# Board.net
KiCad netlist of a schematic drawn in EAGLE
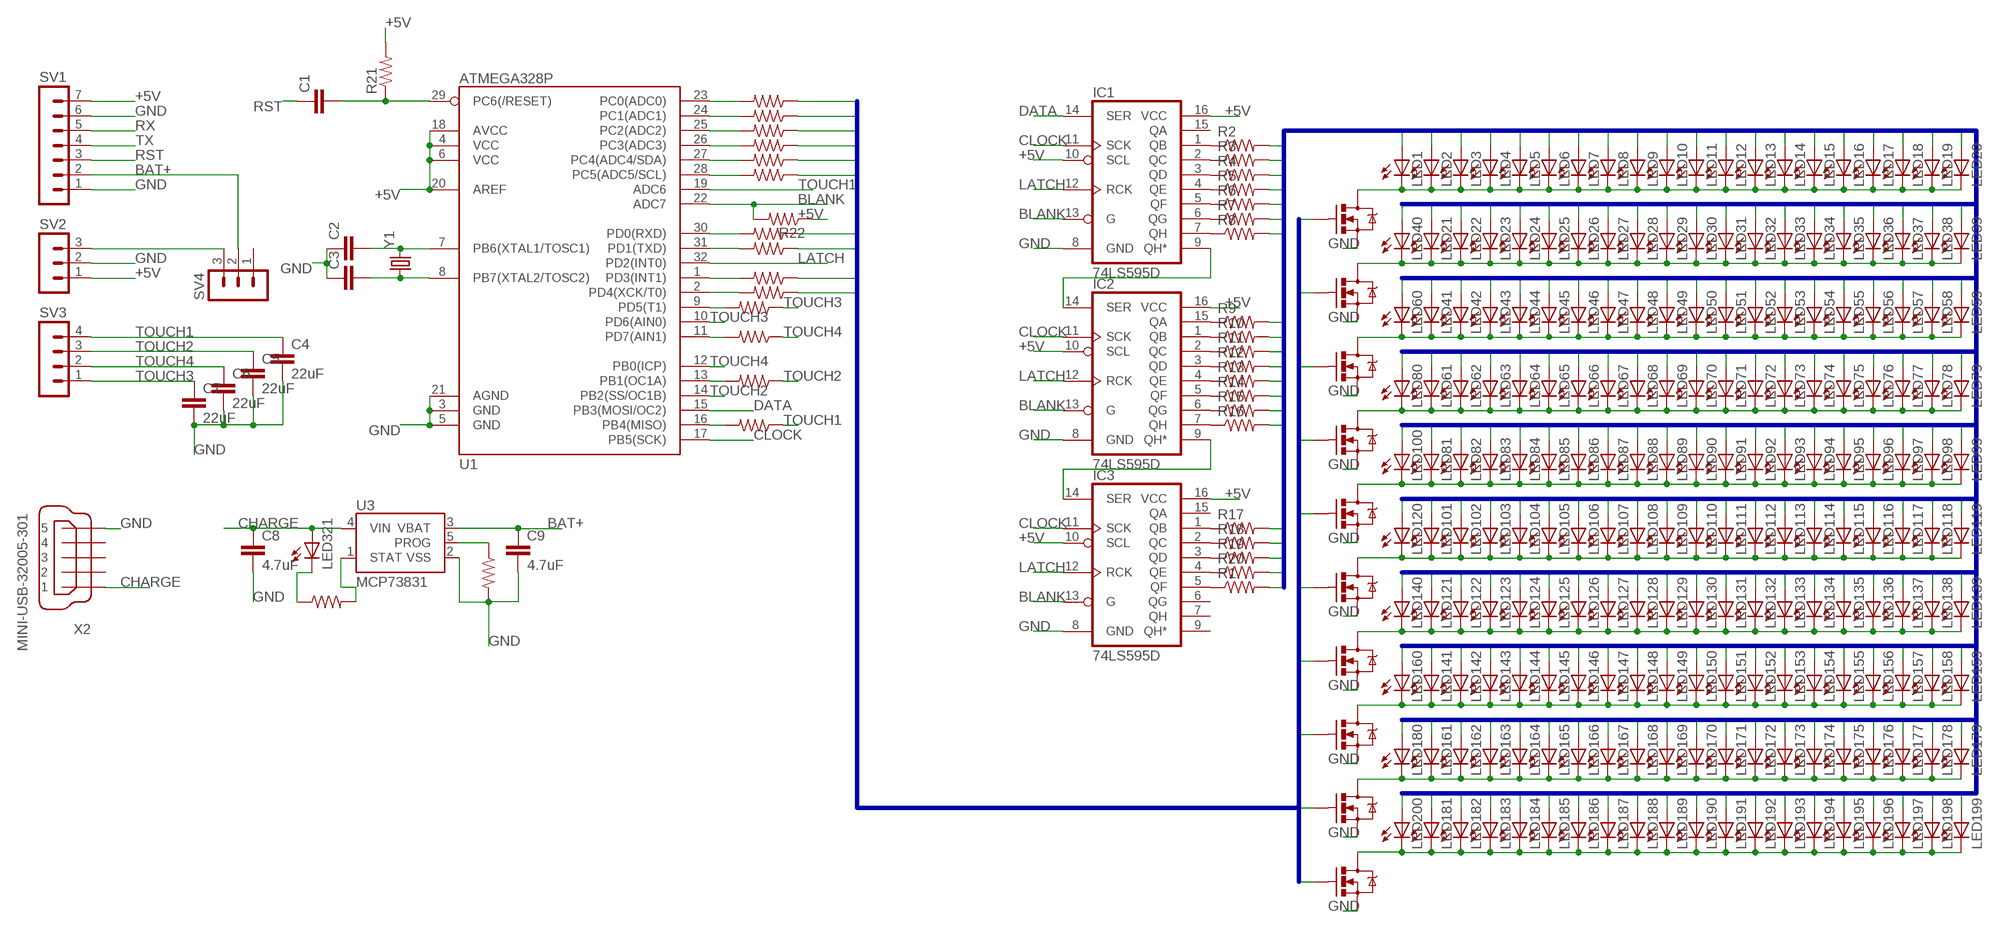
[diagram p0: schematic, sheet 1]

(export (version "E")
  (design (tool "Eeschema 10.0.6"))
  (components
    (comp (ref "2K")
      (value "2K")
      (footprint "eagle-import:0603-RES")
      (libsource (lib "eagle-import") (part "100OHM1/10W1%(0603)"))
    )
    (comp (ref "470R")
      (value "470R")
      (footprint "eagle-import:0603-RES")
      (libsource (lib "eagle-import") (part "100OHM1/10W1%(0603)"))
    )
    (comp (ref "C1")
      (value "CAPPTH1")
      (footprint "eagle-import:CAP-PTH-5MM")
      (libsource (lib "eagle-import") (part "CAPPTH1"))
    )
    (comp (ref "C2")
      (value "22uF")
      (footprint "eagle-import:0805")
      (libsource (lib "eagle-import") (part "22UF-6.3V-20%(0805)"))
    )
    (comp (ref "C3")
      (value "22uF")
      (footprint "eagle-import:0805")
      (libsource (lib "eagle-import") (part "22UF-6.3V-20%(0805)"))
    )
    (comp (ref "C4")
      (value "22uF")
      (footprint "eagle-import:0805")
      (libsource (lib "eagle-import") (part "22UF-6.3V-20%(0805)"))
    )
    (comp (ref "C5")
      (value "22uF")
      (footprint "eagle-import:0805")
      (libsource (lib "eagle-import") (part "22UF-6.3V-20%(0805)"))
    )
    (comp (ref "C6")
      (value "22uF")
      (footprint "eagle-import:0805")
      (libsource (lib "eagle-import") (part "22UF-6.3V-20%(0805)"))
    )
    (comp (ref "C7")
      (value "22uF")
      (footprint "eagle-import:0805")
      (libsource (lib "eagle-import") (part "22UF-6.3V-20%(0805)"))
    )
    (comp (ref "C8")
      (value "4.7uF")
      (footprint "eagle-import:0603-CAP")
      (libsource (lib "eagle-import") (part "0.1UF-25V(+80/-20%)(0603)"))
    )
    (comp (ref "C9")
      (value "4.7uF")
      (footprint "eagle-import:0603-CAP")
      (libsource (lib "eagle-import") (part "0.1UF-25V(+80/-20%)(0603)"))
    )
    (comp (ref "IC1")
      (value "74LS595D")
      (footprint "eagle-import:SO16")
      (libsource (lib "eagle-import") (part "74595DLS"))
    )
    (comp (ref "IC2")
      (value "74LS595D")
      (footprint "eagle-import:SO16")
      (libsource (lib "eagle-import") (part "74595DLS"))
    )
    (comp (ref "IC3")
      (value "74LS595D")
      (footprint "eagle-import:SO16")
      (libsource (lib "eagle-import") (part "74595DLS"))
    )
    (comp (ref "LED1")
      (value "LED0603")
      (footprint "eagle-import:LED-0603")
      (libsource (lib "eagle-import") (part "LED0603"))
    )
    (comp (ref "LED2")
      (value "LED0603")
      (footprint "eagle-import:LED-0603")
      (libsource (lib "eagle-import") (part "LED0603"))
    )
    (comp (ref "LED3")
      (value "LED0603")
      (footprint "eagle-import:LED-0603")
      (libsource (lib "eagle-import") (part "LED0603"))
    )
    (comp (ref "LED4")
      (value "LED0603")
      (footprint "eagle-import:LED-0603")
      (libsource (lib "eagle-import") (part "LED0603"))
    )
    (comp (ref "LED5")
      (value "LED0603")
      (footprint "eagle-import:LED-0603")
      (libsource (lib "eagle-import") (part "LED0603"))
    )
    (comp (ref "LED6")
      (value "LED0603")
      (footprint "eagle-import:LED-0603")
      (libsource (lib "eagle-import") (part "LED0603"))
    )
    (comp (ref "LED7")
      (value "LED0603")
      (footprint "eagle-import:LED-0603")
      (libsource (lib "eagle-import") (part "LED0603"))
    )
    (comp (ref "LED8")
      (value "LED0603")
      (footprint "eagle-import:LED-0603")
      (libsource (lib "eagle-import") (part "LED0603"))
    )
    (comp (ref "LED9")
      (value "LED0603")
      (footprint "eagle-import:LED-0603")
      (libsource (lib "eagle-import") (part "LED0603"))
    )
    (comp (ref "LED10")
      (value "LED0603")
      (footprint "eagle-import:LED-0603")
      (libsource (lib "eagle-import") (part "LED0603"))
    )
    (comp (ref "LED11")
      (value "LED0603")
      (footprint "eagle-import:LED-0603")
      (libsource (lib "eagle-import") (part "LED0603"))
    )
    (comp (ref "LED12")
      (value "LED0603")
      (footprint "eagle-import:LED-0603")
      (libsource (lib "eagle-import") (part "LED0603"))
    )
    (comp (ref "LED13")
      (value "LED0603")
      (footprint "eagle-import:LED-0603")
      (libsource (lib "eagle-import") (part "LED0603"))
    )
    (comp (ref "LED14")
      (value "LED0603")
      (footprint "eagle-import:LED-0603")
      (libsource (lib "eagle-import") (part "LED0603"))
    )
    (comp (ref "LED15")
      (value "LED0603")
      (footprint "eagle-import:LED-0603")
      (libsource (lib "eagle-import") (part "LED0603"))
    )
    (comp (ref "LED16")
      (value "LED0603")
      (footprint "eagle-import:LED-0603")
      (libsource (lib "eagle-import") (part "LED0603"))
    )
    (comp (ref "LED17")
      (value "LED0603")
      (footprint "eagle-import:LED-0603")
      (libsource (lib "eagle-import") (part "LED0603"))
    )
    (comp (ref "LED18")
      (value "LED0603")
      (footprint "eagle-import:LED-0603")
      (libsource (lib "eagle-import") (part "LED0603"))
    )
    (comp (ref "LED19")
      (value "LED0603")
      (footprint "eagle-import:LED-0603")
      (libsource (lib "eagle-import") (part "LED0603"))
    )
    (comp (ref "LED20")
      (value "LED0603")
      (footprint "eagle-import:LED-0603")
      (libsource (lib "eagle-import") (part "LED0603"))
    )
    (comp (ref "LED21")
      (value "LED0603")
      (footprint "eagle-import:LED-0603")
      (libsource (lib "eagle-import") (part "LED0603"))
    )
    (comp (ref "LED22")
      (value "LED0603")
      (footprint "eagle-import:LED-0603")
      (libsource (lib "eagle-import") (part "LED0603"))
    )
    (comp (ref "LED23")
      (value "LED0603")
      (footprint "eagle-import:LED-0603")
      (libsource (lib "eagle-import") (part "LED0603"))
    )
    (comp (ref "LED24")
      (value "LED0603")
      (footprint "eagle-import:LED-0603")
      (libsource (lib "eagle-import") (part "LED0603"))
    )
    (comp (ref "LED25")
      (value "LED0603")
      (footprint "eagle-import:LED-0603")
      (libsource (lib "eagle-import") (part "LED0603"))
    )
    (comp (ref "LED26")
      (value "LED0603")
      (footprint "eagle-import:LED-0603")
      (libsource (lib "eagle-import") (part "LED0603"))
    )
    (comp (ref "LED27")
      (value "LED0603")
      (footprint "eagle-import:LED-0603")
      (libsource (lib "eagle-import") (part "LED0603"))
    )
    (comp (ref "LED28")
      (value "LED0603")
      (footprint "eagle-import:LED-0603")
      (libsource (lib "eagle-import") (part "LED0603"))
    )
    (comp (ref "LED29")
      (value "LED0603")
      (footprint "eagle-import:LED-0603")
      (libsource (lib "eagle-import") (part "LED0603"))
    )
    (comp (ref "LED30")
      (value "LED0603")
      (footprint "eagle-import:LED-0603")
      (libsource (lib "eagle-import") (part "LED0603"))
    )
    (comp (ref "LED31")
      (value "LED0603")
      (footprint "eagle-import:LED-0603")
      (libsource (lib "eagle-import") (part "LED0603"))
    )
    (comp (ref "LED32")
      (value "LED0603")
      (footprint "eagle-import:LED-0603")
      (libsource (lib "eagle-import") (part "LED0603"))
    )
    (comp (ref "LED33")
      (value "LED0603")
      (footprint "eagle-import:LED-0603")
      (libsource (lib "eagle-import") (part "LED0603"))
    )
    (comp (ref "LED34")
      (value "LED0603")
      (footprint "eagle-import:LED-0603")
      (libsource (lib "eagle-import") (part "LED0603"))
    )
    (comp (ref "LED35")
      (value "LED0603")
      (footprint "eagle-import:LED-0603")
      (libsource (lib "eagle-import") (part "LED0603"))
    )
    (comp (ref "LED36")
      (value "LED0603")
      (footprint "eagle-import:LED-0603")
      (libsource (lib "eagle-import") (part "LED0603"))
    )
    (comp (ref "LED37")
      (value "LED0603")
      (footprint "eagle-import:LED-0603")
      (libsource (lib "eagle-import") (part "LED0603"))
    )
    (comp (ref "LED38")
      (value "LED0603")
      (footprint "eagle-import:LED-0603")
      (libsource (lib "eagle-import") (part "LED0603"))
    )
    (comp (ref "LED39")
      (value "LED0603")
      (footprint "eagle-import:LED-0603")
      (libsource (lib "eagle-import") (part "LED0603"))
    )
    (comp (ref "LED40")
      (value "LED0603")
      (footprint "eagle-import:LED-0603")
      (libsource (lib "eagle-import") (part "LED0603"))
    )
    (comp (ref "LED41")
      (value "LED0603")
      (footprint "eagle-import:LED-0603")
      (libsource (lib "eagle-import") (part "LED0603"))
    )
    (comp (ref "LED42")
      (value "LED0603")
      (footprint "eagle-import:LED-0603")
      (libsource (lib "eagle-import") (part "LED0603"))
    )
    (comp (ref "LED43")
      (value "LED0603")
      (footprint "eagle-import:LED-0603")
      (libsource (lib "eagle-import") (part "LED0603"))
    )
    (comp (ref "LED44")
      (value "LED0603")
      (footprint "eagle-import:LED-0603")
      (libsource (lib "eagle-import") (part "LED0603"))
    )
    (comp (ref "LED45")
      (value "LED0603")
      (footprint "eagle-import:LED-0603")
      (libsource (lib "eagle-import") (part "LED0603"))
    )
    (comp (ref "LED46")
      (value "LED0603")
      (footprint "eagle-import:LED-0603")
      (libsource (lib "eagle-import") (part "LED0603"))
    )
    (comp (ref "LED47")
      (value "LED0603")
      (footprint "eagle-import:LED-0603")
      (libsource (lib "eagle-import") (part "LED0603"))
    )
    (comp (ref "LED48")
      (value "LED0603")
      (footprint "eagle-import:LED-0603")
      (libsource (lib "eagle-import") (part "LED0603"))
    )
    (comp (ref "LED49")
      (value "LED0603")
      (footprint "eagle-import:LED-0603")
      (libsource (lib "eagle-import") (part "LED0603"))
    )
    (comp (ref "LED50")
      (value "LED0603")
      (footprint "eagle-import:LED-0603")
      (libsource (lib "eagle-import") (part "LED0603"))
    )
    (comp (ref "LED51")
      (value "LED0603")
      (footprint "eagle-import:LED-0603")
      (libsource (lib "eagle-import") (part "LED0603"))
    )
    (comp (ref "LED52")
      (value "LED0603")
      (footprint "eagle-import:LED-0603")
      (libsource (lib "eagle-import") (part "LED0603"))
    )
    (comp (ref "LED53")
      (value "LED0603")
      (footprint "eagle-import:LED-0603")
      (libsource (lib "eagle-import") (part "LED0603"))
    )
    (comp (ref "LED54")
      (value "LED0603")
      (footprint "eagle-import:LED-0603")
      (libsource (lib "eagle-import") (part "LED0603"))
    )
    (comp (ref "LED55")
      (value "LED0603")
      (footprint "eagle-import:LED-0603")
      (libsource (lib "eagle-import") (part "LED0603"))
    )
    (comp (ref "LED56")
      (value "LED0603")
      (footprint "eagle-import:LED-0603")
      (libsource (lib "eagle-import") (part "LED0603"))
    )
    (comp (ref "LED57")
      (value "LED0603")
      (footprint "eagle-import:LED-0603")
      (libsource (lib "eagle-import") (part "LED0603"))
    )
    (comp (ref "LED58")
      (value "LED0603")
      (footprint "eagle-import:LED-0603")
      (libsource (lib "eagle-import") (part "LED0603"))
    )
    (comp (ref "LED59")
      (value "LED0603")
      (footprint "eagle-import:LED-0603")
      (libsource (lib "eagle-import") (part "LED0603"))
    )
    (comp (ref "LED60")
      (value "LED0603")
      (footprint "eagle-import:LED-0603")
      (libsource (lib "eagle-import") (part "LED0603"))
    )
    (comp (ref "LED61")
      (value "LED0603")
      (footprint "eagle-import:LED-0603")
      (libsource (lib "eagle-import") (part "LED0603"))
    )
    (comp (ref "LED62")
      (value "LED0603")
      (footprint "eagle-import:LED-0603")
      (libsource (lib "eagle-import") (part "LED0603"))
    )
    (comp (ref "LED63")
      (value "LED0603")
      (footprint "eagle-import:LED-0603")
      (libsource (lib "eagle-import") (part "LED0603"))
    )
    (comp (ref "LED64")
      (value "LED0603")
      (footprint "eagle-import:LED-0603")
      (libsource (lib "eagle-import") (part "LED0603"))
    )
    (comp (ref "LED65")
      (value "LED0603")
      (footprint "eagle-import:LED-0603")
      (libsource (lib "eagle-import") (part "LED0603"))
    )
    (comp (ref "LED66")
      (value "LED0603")
      (footprint "eagle-import:LED-0603")
      (libsource (lib "eagle-import") (part "LED0603"))
    )
    (comp (ref "LED67")
      (value "LED0603")
      (footprint "eagle-import:LED-0603")
      (libsource (lib "eagle-import") (part "LED0603"))
    )
    (comp (ref "LED68")
      (value "LED0603")
      (footprint "eagle-import:LED-0603")
      (libsource (lib "eagle-import") (part "LED0603"))
    )
    (comp (ref "LED69")
      (value "LED0603")
      (footprint "eagle-import:LED-0603")
      (libsource (lib "eagle-import") (part "LED0603"))
    )
    (comp (ref "LED70")
      (value "LED0603")
      (footprint "eagle-import:LED-0603")
      (libsource (lib "eagle-import") (part "LED0603"))
    )
    (comp (ref "LED71")
      (value "LED0603")
      (footprint "eagle-import:LED-0603")
      (libsource (lib "eagle-import") (part "LED0603"))
    )
    (comp (ref "LED72")
      (value "LED0603")
      (footprint "eagle-import:LED-0603")
      (libsource (lib "eagle-import") (part "LED0603"))
    )
    (comp (ref "LED73")
      (value "LED0603")
      (footprint "eagle-import:LED-0603")
      (libsource (lib "eagle-import") (part "LED0603"))
    )
    (comp (ref "LED74")
      (value "LED0603")
      (footprint "eagle-import:LED-0603")
      (libsource (lib "eagle-import") (part "LED0603"))
    )
    (comp (ref "LED75")
      (value "LED0603")
      (footprint "eagle-import:LED-0603")
      (libsource (lib "eagle-import") (part "LED0603"))
    )
    (comp (ref "LED76")
      (value "LED0603")
      (footprint "eagle-import:LED-0603")
      (libsource (lib "eagle-import") (part "LED0603"))
    )
    (comp (ref "LED77")
      (value "LED0603")
      (footprint "eagle-import:LED-0603")
      (libsource (lib "eagle-import") (part "LED0603"))
    )
    (comp (ref "LED78")
      (value "LED0603")
      (footprint "eagle-import:LED-0603")
      (libsource (lib "eagle-import") (part "LED0603"))
    )
    (comp (ref "LED79")
      (value "LED0603")
      (footprint "eagle-import:LED-0603")
      (libsource (lib "eagle-import") (part "LED0603"))
    )
    (comp (ref "LED80")
      (value "LED0603")
      (footprint "eagle-import:LED-0603")
      (libsource (lib "eagle-import") (part "LED0603"))
    )
    (comp (ref "LED81")
      (value "LED0603")
      (footprint "eagle-import:LED-0603")
      (libsource (lib "eagle-import") (part "LED0603"))
    )
    (comp (ref "LED82")
      (value "LED0603")
      (footprint "eagle-import:LED-0603")
      (libsource (lib "eagle-import") (part "LED0603"))
    )
    (comp (ref "LED83")
      (value "LED0603")
      (footprint "eagle-import:LED-0603")
      (libsource (lib "eagle-import") (part "LED0603"))
    )
    (comp (ref "LED84")
      (value "LED0603")
      (footprint "eagle-import:LED-0603")
      (libsource (lib "eagle-import") (part "LED0603"))
    )
    (comp (ref "LED85")
      (value "LED0603")
      (footprint "eagle-import:LED-0603")
      (libsource (lib "eagle-import") (part "LED0603"))
    )
    (comp (ref "LED86")
      (value "LED0603")
      (footprint "eagle-import:LED-0603")
      (libsource (lib "eagle-import") (part "LED0603"))
    )
    (comp (ref "LED87")
      (value "LED0603")
      (footprint "eagle-import:LED-0603")
      (libsource (lib "eagle-import") (part "LED0603"))
    )
    (comp (ref "LED88")
      (value "LED0603")
      (footprint "eagle-import:LED-0603")
      (libsource (lib "eagle-import") (part "LED0603"))
    )
    (comp (ref "LED89")
      (value "LED0603")
      (footprint "eagle-import:LED-0603")
      (libsource (lib "eagle-import") (part "LED0603"))
    )
    (comp (ref "LED90")
      (value "LED0603")
      (footprint "eagle-import:LED-0603")
      (libsource (lib "eagle-import") (part "LED0603"))
    )
    (comp (ref "LED91")
      (value "LED0603")
      (footprint "eagle-import:LED-0603")
      (libsource (lib "eagle-import") (part "LED0603"))
    )
    (comp (ref "LED92")
      (value "LED0603")
      (footprint "eagle-import:LED-0603")
      (libsource (lib "eagle-import") (part "LED0603"))
    )
    (comp (ref "LED93")
      (value "LED0603")
      (footprint "eagle-import:LED-0603")
      (libsource (lib "eagle-import") (part "LED0603"))
    )
    (comp (ref "LED94")
      (value "LED0603")
      (footprint "eagle-import:LED-0603")
      (libsource (lib "eagle-import") (part "LED0603"))
    )
    (comp (ref "LED95")
      (value "LED0603")
      (footprint "eagle-import:LED-0603")
      (libsource (lib "eagle-import") (part "LED0603"))
    )
    (comp (ref "LED96")
      (value "LED0603")
      (footprint "eagle-import:LED-0603")
      (libsource (lib "eagle-import") (part "LED0603"))
    )
    (comp (ref "LED97")
      (value "LED0603")
      (footprint "eagle-import:LED-0603")
      (libsource (lib "eagle-import") (part "LED0603"))
    )
    (comp (ref "LED98")
      (value "LED0603")
      (footprint "eagle-import:LED-0603")
      (libsource (lib "eagle-import") (part "LED0603"))
    )
    (comp (ref "LED99")
      (value "LED0603")
      (footprint "eagle-import:LED-0603")
      (libsource (lib "eagle-import") (part "LED0603"))
    )
    (comp (ref "LED100")
      (value "LED0603")
      (footprint "eagle-import:LED-0603")
      (libsource (lib "eagle-import") (part "LED0603"))
    )
    (comp (ref "LED101")
      (value "LED0603")
      (footprint "eagle-import:LED-0603")
      (libsource (lib "eagle-import") (part "LED0603"))
    )
    (comp (ref "LED102")
      (value "LED0603")
      (footprint "eagle-import:LED-0603")
      (libsource (lib "eagle-import") (part "LED0603"))
    )
    (comp (ref "LED103")
      (value "LED0603")
      (footprint "eagle-import:LED-0603")
      (libsource (lib "eagle-import") (part "LED0603"))
    )
    (comp (ref "LED104")
      (value "LED0603")
      (footprint "eagle-import:LED-0603")
      (libsource (lib "eagle-import") (part "LED0603"))
    )
    (comp (ref "LED105")
      (value "LED0603")
      (footprint "eagle-import:LED-0603")
      (libsource (lib "eagle-import") (part "LED0603"))
    )
    (comp (ref "LED106")
      (value "LED0603")
      (footprint "eagle-import:LED-0603")
      (libsource (lib "eagle-import") (part "LED0603"))
    )
    (comp (ref "LED107")
      (value "LED0603")
      (footprint "eagle-import:LED-0603")
      (libsource (lib "eagle-import") (part "LED0603"))
    )
    (comp (ref "LED108")
      (value "LED0603")
      (footprint "eagle-import:LED-0603")
      (libsource (lib "eagle-import") (part "LED0603"))
    )
    (comp (ref "LED109")
      (value "LED0603")
      (footprint "eagle-import:LED-0603")
      (libsource (lib "eagle-import") (part "LED0603"))
    )
    (comp (ref "LED110")
      (value "LED0603")
      (footprint "eagle-import:LED-0603")
      (libsource (lib "eagle-import") (part "LED0603"))
    )
    (comp (ref "LED111")
      (value "LED0603")
      (footprint "eagle-import:LED-0603")
      (libsource (lib "eagle-import") (part "LED0603"))
    )
    (comp (ref "LED112")
      (value "LED0603")
      (footprint "eagle-import:LED-0603")
      (libsource (lib "eagle-import") (part "LED0603"))
    )
    (comp (ref "LED113")
      (value "LED0603")
      (footprint "eagle-import:LED-0603")
      (libsource (lib "eagle-import") (part "LED0603"))
    )
    (comp (ref "LED114")
      (value "LED0603")
      (footprint "eagle-import:LED-0603")
      (libsource (lib "eagle-import") (part "LED0603"))
    )
    (comp (ref "LED115")
      (value "LED0603")
      (footprint "eagle-import:LED-0603")
      (libsource (lib "eagle-import") (part "LED0603"))
    )
    (comp (ref "LED116")
      (value "LED0603")
      (footprint "eagle-import:LED-0603")
      (libsource (lib "eagle-import") (part "LED0603"))
    )
    (comp (ref "LED117")
      (value "LED0603")
      (footprint "eagle-import:LED-0603")
      (libsource (lib "eagle-import") (part "LED0603"))
    )
    (comp (ref "LED118")
      (value "LED0603")
      (footprint "eagle-import:LED-0603")
      (libsource (lib "eagle-import") (part "LED0603"))
    )
    (comp (ref "LED119")
      (value "LED0603")
      (footprint "eagle-import:LED-0603")
      (libsource (lib "eagle-import") (part "LED0603"))
    )
    (comp (ref "LED120")
      (value "LED0603")
      (footprint "eagle-import:LED-0603")
      (libsource (lib "eagle-import") (part "LED0603"))
    )
    (comp (ref "LED121")
      (value "LED0603")
      (footprint "eagle-import:LED-0603")
      (libsource (lib "eagle-import") (part "LED0603"))
    )
    (comp (ref "LED122")
      (value "LED0603")
      (footprint "eagle-import:LED-0603")
      (libsource (lib "eagle-import") (part "LED0603"))
    )
    (comp (ref "LED123")
      (value "LED0603")
      (footprint "eagle-import:LED-0603")
      (libsource (lib "eagle-import") (part "LED0603"))
    )
    (comp (ref "LED124")
      (value "LED0603")
      (footprint "eagle-import:LED-0603")
      (libsource (lib "eagle-import") (part "LED0603"))
    )
    (comp (ref "LED125")
      (value "LED0603")
      (footprint "eagle-import:LED-0603")
      (libsource (lib "eagle-import") (part "LED0603"))
    )
    (comp (ref "LED126")
      (value "LED0603")
      (footprint "eagle-import:LED-0603")
      (libsource (lib "eagle-import") (part "LED0603"))
    )
    (comp (ref "LED127")
      (value "LED0603")
      (footprint "eagle-import:LED-0603")
      (libsource (lib "eagle-import") (part "LED0603"))
    )
    (comp (ref "LED128")
      (value "LED0603")
      (footprint "eagle-import:LED-0603")
      (libsource (lib "eagle-import") (part "LED0603"))
    )
    (comp (ref "LED129")
      (value "LED0603")
      (footprint "eagle-import:LED-0603")
      (libsource (lib "eagle-import") (part "LED0603"))
    )
    (comp (ref "LED130")
      (value "LED0603")
      (footprint "eagle-import:LED-0603")
      (libsource (lib "eagle-import") (part "LED0603"))
    )
    (comp (ref "LED131")
      (value "LED0603")
      (footprint "eagle-import:LED-0603")
      (libsource (lib "eagle-import") (part "LED0603"))
    )
    (comp (ref "LED132")
      (value "LED0603")
      (footprint "eagle-import:LED-0603")
      (libsource (lib "eagle-import") (part "LED0603"))
    )
    (comp (ref "LED133")
      (value "LED0603")
      (footprint "eagle-import:LED-0603")
      (libsource (lib "eagle-import") (part "LED0603"))
    )
    (comp (ref "LED134")
      (value "LED0603")
      (footprint "eagle-import:LED-0603")
      (libsource (lib "eagle-import") (part "LED0603"))
    )
    (comp (ref "LED135")
      (value "LED0603")
      (footprint "eagle-import:LED-0603")
      (libsource (lib "eagle-import") (part "LED0603"))
    )
    (comp (ref "LED136")
      (value "LED0603")
      (footprint "eagle-import:LED-0603")
      (libsource (lib "eagle-import") (part "LED0603"))
    )
    (comp (ref "LED137")
      (value "LED0603")
      (footprint "eagle-import:LED-0603")
      (libsource (lib "eagle-import") (part "LED0603"))
    )
    (comp (ref "LED138")
      (value "LED0603")
      (footprint "eagle-import:LED-0603")
      (libsource (lib "eagle-import") (part "LED0603"))
    )
    (comp (ref "LED139")
      (value "LED0603")
      (footprint "eagle-import:LED-0603")
      (libsource (lib "eagle-import") (part "LED0603"))
    )
    (comp (ref "LED140")
      (value "LED0603")
      (footprint "eagle-import:LED-0603")
      (libsource (lib "eagle-import") (part "LED0603"))
    )
    (comp (ref "LED141")
      (value "LED0603")
      (footprint "eagle-import:LED-0603")
      (libsource (lib "eagle-import") (part "LED0603"))
    )
    (comp (ref "LED142")
      (value "LED0603")
      (footprint "eagle-import:LED-0603")
      (libsource (lib "eagle-import") (part "LED0603"))
    )
    (comp (ref "LED143")
      (value "LED0603")
      (footprint "eagle-import:LED-0603")
      (libsource (lib "eagle-import") (part "LED0603"))
    )
    (comp (ref "LED144")
      (value "LED0603")
      (footprint "eagle-import:LED-0603")
      (libsource (lib "eagle-import") (part "LED0603"))
    )
    (comp (ref "LED145")
      (value "LED0603")
      (footprint "eagle-import:LED-0603")
      (libsource (lib "eagle-import") (part "LED0603"))
    )
    (comp (ref "LED146")
      (value "LED0603")
      (footprint "eagle-import:LED-0603")
      (libsource (lib "eagle-import") (part "LED0603"))
    )
    (comp (ref "LED147")
      (value "LED0603")
      (footprint "eagle-import:LED-0603")
      (libsource (lib "eagle-import") (part "LED0603"))
    )
    (comp (ref "LED148")
      (value "LED0603")
      (footprint "eagle-import:LED-0603")
      (libsource (lib "eagle-import") (part "LED0603"))
    )
    (comp (ref "LED149")
      (value "LED0603")
      (footprint "eagle-import:LED-0603")
      (libsource (lib "eagle-import") (part "LED0603"))
    )
    (comp (ref "LED150")
      (value "LED0603")
      (footprint "eagle-import:LED-0603")
      (libsource (lib "eagle-import") (part "LED0603"))
    )
    (comp (ref "LED151")
      (value "LED0603")
      (footprint "eagle-import:LED-0603")
      (libsource (lib "eagle-import") (part "LED0603"))
    )
    (comp (ref "LED152")
      (value "LED0603")
      (footprint "eagle-import:LED-0603")
      (libsource (lib "eagle-import") (part "LED0603"))
    )
    (comp (ref "LED153")
      (value "LED0603")
      (footprint "eagle-import:LED-0603")
      (libsource (lib "eagle-import") (part "LED0603"))
    )
    (comp (ref "LED154")
      (value "LED0603")
      (footprint "eagle-import:LED-0603")
      (libsource (lib "eagle-import") (part "LED0603"))
    )
    (comp (ref "LED155")
      (value "LED0603")
      (footprint "eagle-import:LED-0603")
      (libsource (lib "eagle-import") (part "LED0603"))
    )
    (comp (ref "LED156")
      (value "LED0603")
      (footprint "eagle-import:LED-0603")
      (libsource (lib "eagle-import") (part "LED0603"))
    )
    (comp (ref "LED157")
      (value "LED0603")
      (footprint "eagle-import:LED-0603")
      (libsource (lib "eagle-import") (part "LED0603"))
    )
    (comp (ref "LED158")
      (value "LED0603")
      (footprint "eagle-import:LED-0603")
      (libsource (lib "eagle-import") (part "LED0603"))
    )
    (comp (ref "LED159")
      (value "LED0603")
      (footprint "eagle-import:LED-0603")
      (libsource (lib "eagle-import") (part "LED0603"))
    )
    (comp (ref "LED160")
      (value "LED0603")
      (footprint "eagle-import:LED-0603")
      (libsource (lib "eagle-import") (part "LED0603"))
    )
    (comp (ref "LED161")
      (value "LED0603")
      (footprint "eagle-import:LED-0603")
      (libsource (lib "eagle-import") (part "LED0603"))
    )
    (comp (ref "LED162")
      (value "LED0603")
      (footprint "eagle-import:LED-0603")
      (libsource (lib "eagle-import") (part "LED0603"))
    )
    (comp (ref "LED163")
      (value "LED0603")
      (footprint "eagle-import:LED-0603")
      (libsource (lib "eagle-import") (part "LED0603"))
    )
    (comp (ref "LED164")
      (value "LED0603")
      (footprint "eagle-import:LED-0603")
      (libsource (lib "eagle-import") (part "LED0603"))
    )
    (comp (ref "LED165")
      (value "LED0603")
      (footprint "eagle-import:LED-0603")
      (libsource (lib "eagle-import") (part "LED0603"))
    )
    (comp (ref "LED166")
      (value "LED0603")
      (footprint "eagle-import:LED-0603")
      (libsource (lib "eagle-import") (part "LED0603"))
    )
    (comp (ref "LED167")
      (value "LED0603")
      (footprint "eagle-import:LED-0603")
      (libsource (lib "eagle-import") (part "LED0603"))
    )
    (comp (ref "LED168")
      (value "LED0603")
      (footprint "eagle-import:LED-0603")
      (libsource (lib "eagle-import") (part "LED0603"))
    )
    (comp (ref "LED169")
      (value "LED0603")
      (footprint "eagle-import:LED-0603")
      (libsource (lib "eagle-import") (part "LED0603"))
    )
    (comp (ref "LED170")
      (value "LED0603")
      (footprint "eagle-import:LED-0603")
      (libsource (lib "eagle-import") (part "LED0603"))
    )
    (comp (ref "LED171")
      (value "LED0603")
      (footprint "eagle-import:LED-0603")
      (libsource (lib "eagle-import") (part "LED0603"))
    )
    (comp (ref "LED172")
      (value "LED0603")
      (footprint "eagle-import:LED-0603")
      (libsource (lib "eagle-import") (part "LED0603"))
    )
    (comp (ref "LED173")
      (value "LED0603")
      (footprint "eagle-import:LED-0603")
      (libsource (lib "eagle-import") (part "LED0603"))
    )
    (comp (ref "LED174")
      (value "LED0603")
      (footprint "eagle-import:LED-0603")
      (libsource (lib "eagle-import") (part "LED0603"))
    )
    (comp (ref "LED175")
      (value "LED0603")
      (footprint "eagle-import:LED-0603")
      (libsource (lib "eagle-import") (part "LED0603"))
    )
    (comp (ref "LED176")
      (value "LED0603")
      (footprint "eagle-import:LED-0603")
      (libsource (lib "eagle-import") (part "LED0603"))
    )
    (comp (ref "LED177")
      (value "LED0603")
      (footprint "eagle-import:LED-0603")
      (libsource (lib "eagle-import") (part "LED0603"))
    )
    (comp (ref "LED178")
      (value "LED0603")
      (footprint "eagle-import:LED-0603")
      (libsource (lib "eagle-import") (part "LED0603"))
    )
    (comp (ref "LED179")
      (value "LED0603")
      (footprint "eagle-import:LED-0603")
      (libsource (lib "eagle-import") (part "LED0603"))
    )
    (comp (ref "LED180")
      (value "LED0603")
      (footprint "eagle-import:LED-0603")
      (libsource (lib "eagle-import") (part "LED0603"))
    )
    (comp (ref "LED181")
      (value "LED0603")
      (footprint "eagle-import:LED-0603")
      (libsource (lib "eagle-import") (part "LED0603"))
    )
    (comp (ref "LED182")
      (value "LED0603")
      (footprint "eagle-import:LED-0603")
      (libsource (lib "eagle-import") (part "LED0603"))
    )
    (comp (ref "LED183")
      (value "LED0603")
      (footprint "eagle-import:LED-0603")
      (libsource (lib "eagle-import") (part "LED0603"))
    )
    (comp (ref "LED184")
      (value "LED0603")
      (footprint "eagle-import:LED-0603")
      (libsource (lib "eagle-import") (part "LED0603"))
    )
    (comp (ref "LED185")
      (value "LED0603")
      (footprint "eagle-import:LED-0603")
      (libsource (lib "eagle-import") (part "LED0603"))
    )
    (comp (ref "LED186")
      (value "LED0603")
      (footprint "eagle-import:LED-0603")
      (libsource (lib "eagle-import") (part "LED0603"))
    )
    (comp (ref "LED187")
      (value "LED0603")
      (footprint "eagle-import:LED-0603")
      (libsource (lib "eagle-import") (part "LED0603"))
    )
    (comp (ref "LED188")
      (value "LED0603")
      (footprint "eagle-import:LED-0603")
      (libsource (lib "eagle-import") (part "LED0603"))
    )
    (comp (ref "LED189")
      (value "LED0603")
      (footprint "eagle-import:LED-0603")
      (libsource (lib "eagle-import") (part "LED0603"))
    )
    (comp (ref "LED190")
      (value "LED0603")
      (footprint "eagle-import:LED-0603")
      (libsource (lib "eagle-import") (part "LED0603"))
    )
    (comp (ref "LED191")
      (value "LED0603")
      (footprint "eagle-import:LED-0603")
      (libsource (lib "eagle-import") (part "LED0603"))
    )
    (comp (ref "LED192")
      (value "LED0603")
      (footprint "eagle-import:LED-0603")
      (libsource (lib "eagle-import") (part "LED0603"))
    )
    (comp (ref "LED193")
      (value "LED0603")
      (footprint "eagle-import:LED-0603")
      (libsource (lib "eagle-import") (part "LED0603"))
    )
    (comp (ref "LED194")
      (value "LED0603")
      (footprint "eagle-import:LED-0603")
      (libsource (lib "eagle-import") (part "LED0603"))
    )
    (comp (ref "LED195")
      (value "LED0603")
      (footprint "eagle-import:LED-0603")
      (libsource (lib "eagle-import") (part "LED0603"))
    )
    (comp (ref "LED196")
      (value "LED0603")
      (footprint "eagle-import:LED-0603")
      (libsource (lib "eagle-import") (part "LED0603"))
    )
    (comp (ref "LED197")
      (value "LED0603")
      (footprint "eagle-import:LED-0603")
      (libsource (lib "eagle-import") (part "LED0603"))
    )
    (comp (ref "LED198")
      (value "LED0603")
      (footprint "eagle-import:LED-0603")
      (libsource (lib "eagle-import") (part "LED0603"))
    )
    (comp (ref "LED199")
      (value "LED0603")
      (footprint "eagle-import:LED-0603")
      (libsource (lib "eagle-import") (part "LED0603"))
    )
    (comp (ref "LED200")
      (value "LED0603")
      (footprint "eagle-import:LED-0603")
      (libsource (lib "eagle-import") (part "LED0603"))
    )
    (comp (ref "LED321")
      (value "LED0603")
      (footprint "eagle-import:LED-0603")
      (libsource (lib "eagle-import") (part "LED0603"))
    )
    (comp (ref "Q1")
      (value "MOSFET-NCHANNELBSS123LT1G")
      (footprint "eagle-import:SOT23")
      (libsource (lib "eagle-import") (part "MOSFET-NCHANNELBSS123LT1G"))
    )
    (comp (ref "Q2")
      (value "MOSFET-NCHANNELBSS123LT1G")
      (footprint "eagle-import:SOT23")
      (libsource (lib "eagle-import") (part "MOSFET-NCHANNELBSS123LT1G"))
    )
    (comp (ref "Q3")
      (value "MOSFET-NCHANNELBSS123LT1G")
      (footprint "eagle-import:SOT23")
      (libsource (lib "eagle-import") (part "MOSFET-NCHANNELBSS123LT1G"))
    )
    (comp (ref "Q6")
      (value "MOSFET-NCHANNELBSS123LT1G")
      (footprint "eagle-import:SOT23")
      (libsource (lib "eagle-import") (part "MOSFET-NCHANNELBSS123LT1G"))
    )
    (comp (ref "Q8")
      (value "MOSFET-NCHANNELBSS123LT1G")
      (footprint "eagle-import:SOT23")
      (libsource (lib "eagle-import") (part "MOSFET-NCHANNELBSS123LT1G"))
    )
    (comp (ref "Q10")
      (value "MOSFET-NCHANNELBSS123LT1G")
      (footprint "eagle-import:SOT23")
      (libsource (lib "eagle-import") (part "MOSFET-NCHANNELBSS123LT1G"))
    )
    (comp (ref "Q12")
      (value "MOSFET-NCHANNELBSS123LT1G")
      (footprint "eagle-import:SOT23")
      (libsource (lib "eagle-import") (part "MOSFET-NCHANNELBSS123LT1G"))
    )
    (comp (ref "Q14")
      (value "MOSFET-NCHANNELBSS123LT1G")
      (footprint "eagle-import:SOT23")
      (libsource (lib "eagle-import") (part "MOSFET-NCHANNELBSS123LT1G"))
    )
    (comp (ref "Q16")
      (value "MOSFET-NCHANNELBSS123LT1G")
      (footprint "eagle-import:SOT23")
      (libsource (lib "eagle-import") (part "MOSFET-NCHANNELBSS123LT1G"))
    )
    (comp (ref "Q19")
      (value "MOSFET-NCHANNELBSS123LT1G")
      (footprint "eagle-import:SOT23")
      (libsource (lib "eagle-import") (part "MOSFET-NCHANNELBSS123LT1G"))
    )
    (comp (ref "R1")
      (value "100")
      (footprint "eagle-import:0603-RES")
      (libsource (lib "eagle-import") (part "100OHM1/10W1%(0603)"))
    )
    (comp (ref "R2")
      (value "100")
      (footprint "eagle-import:0603-RES")
      (libsource (lib "eagle-import") (part "100OHM1/10W1%(0603)"))
    )
    (comp (ref "R3")
      (value "100")
      (footprint "eagle-import:0603-RES")
      (libsource (lib "eagle-import") (part "100OHM1/10W1%(0603)"))
    )
    (comp (ref "R4")
      (value "100")
      (footprint "eagle-import:0603-RES")
      (libsource (lib "eagle-import") (part "100OHM1/10W1%(0603)"))
    )
    (comp (ref "R5")
      (value "100")
      (footprint "eagle-import:0603-RES")
      (libsource (lib "eagle-import") (part "100OHM1/10W1%(0603)"))
    )
    (comp (ref "R6")
      (value "100")
      (footprint "eagle-import:0603-RES")
      (libsource (lib "eagle-import") (part "100OHM1/10W1%(0603)"))
    )
    (comp (ref "R7")
      (value "100")
      (footprint "eagle-import:0603-RES")
      (libsource (lib "eagle-import") (part "100OHM1/10W1%(0603)"))
    )
    (comp (ref "R8")
      (value "100")
      (footprint "eagle-import:0603-RES")
      (libsource (lib "eagle-import") (part "100OHM1/10W1%(0603)"))
    )
    (comp (ref "R9")
      (value "100")
      (footprint "eagle-import:0603-RES")
      (libsource (lib "eagle-import") (part "100OHM1/10W1%(0603)"))
    )
    (comp (ref "R10")
      (value "100")
      (footprint "eagle-import:0603-RES")
      (libsource (lib "eagle-import") (part "100OHM1/10W1%(0603)"))
    )
    (comp (ref "R11")
      (value "100")
      (footprint "eagle-import:0603-RES")
      (libsource (lib "eagle-import") (part "100OHM1/10W1%(0603)"))
    )
    (comp (ref "R12")
      (value "100")
      (footprint "eagle-import:0603-RES")
      (libsource (lib "eagle-import") (part "100OHM1/10W1%(0603)"))
    )
    (comp (ref "R13")
      (value "100")
      (footprint "eagle-import:0603-RES")
      (libsource (lib "eagle-import") (part "100OHM1/10W1%(0603)"))
    )
    (comp (ref "R14")
      (value "100")
      (footprint "eagle-import:0603-RES")
      (libsource (lib "eagle-import") (part "100OHM1/10W1%(0603)"))
    )
    (comp (ref "R15")
      (value "100")
      (footprint "eagle-import:0603-RES")
      (libsource (lib "eagle-import") (part "100OHM1/10W1%(0603)"))
    )
    (comp (ref "R16")
      (value "100")
      (footprint "eagle-import:0603-RES")
      (libsource (lib "eagle-import") (part "100OHM1/10W1%(0603)"))
    )
    (comp (ref "R17")
      (value "100")
      (footprint "eagle-import:0603-RES")
      (libsource (lib "eagle-import") (part "100OHM1/10W1%(0603)"))
    )
    (comp (ref "R18")
      (value "100")
      (footprint "eagle-import:0603-RES")
      (libsource (lib "eagle-import") (part "100OHM1/10W1%(0603)"))
    )
    (comp (ref "R19")
      (value "100")
      (footprint "eagle-import:0603-RES")
      (libsource (lib "eagle-import") (part "100OHM1/10W1%(0603)"))
    )
    (comp (ref "R20")
      (value "100")
      (footprint "eagle-import:0603-RES")
      (libsource (lib "eagle-import") (part "100OHM1/10W1%(0603)"))
    )
    (comp (ref "R21")
      (value "10K")
      (footprint "eagle-import:0603-RES")
      (libsource (lib "eagle-import") (part "100OHM1/10W1%(0603)"))
    )
    (comp (ref "R22")
      (value "10K")
      (footprint "eagle-import:0603-RES")
      (libsource (lib "eagle-import") (part "100OHM1/10W1%(0603)"))
    )
    (comp (ref "R23")
      (value "1M")
      (footprint "eagle-import:0603-RES")
      (libsource (lib "eagle-import") (part "100OHM1/10W1%(0603)"))
    )
    (comp (ref "R24")
      (value "1M")
      (footprint "eagle-import:0603-RES")
      (libsource (lib "eagle-import") (part "100OHM1/10W1%(0603)"))
    )
    (comp (ref "R26")
      (value "1M")
      (footprint "eagle-import:0603-RES")
      (libsource (lib "eagle-import") (part "100OHM1/10W1%(0603)"))
    )
    (comp (ref "R30")
      (value "100")
      (footprint "eagle-import:0603-RES")
      (libsource (lib "eagle-import") (part "100OHM1/10W1%(0603)"))
    )
    (comp (ref "R31")
      (value "100")
      (footprint "eagle-import:0603-RES")
      (libsource (lib "eagle-import") (part "100OHM1/10W1%(0603)"))
    )
    (comp (ref "R32")
      (value "100")
      (footprint "eagle-import:0603-RES")
      (libsource (lib "eagle-import") (part "100OHM1/10W1%(0603)"))
    )
    (comp (ref "R33")
      (value "100")
      (footprint "eagle-import:0603-RES")
      (libsource (lib "eagle-import") (part "100OHM1/10W1%(0603)"))
    )
    (comp (ref "R34")
      (value "100")
      (footprint "eagle-import:0603-RES")
      (libsource (lib "eagle-import") (part "100OHM1/10W1%(0603)"))
    )
    (comp (ref "R35")
      (value "100")
      (footprint "eagle-import:0603-RES")
      (libsource (lib "eagle-import") (part "100OHM1/10W1%(0603)"))
    )
    (comp (ref "R36")
      (value "100")
      (footprint "eagle-import:0603-RES")
      (libsource (lib "eagle-import") (part "100OHM1/10W1%(0603)"))
    )
    (comp (ref "R37")
      (value "100")
      (footprint "eagle-import:0603-RES")
      (libsource (lib "eagle-import") (part "100OHM1/10W1%(0603)"))
    )
    (comp (ref "R38")
      (value "100")
      (footprint "eagle-import:0603-RES")
      (libsource (lib "eagle-import") (part "100OHM1/10W1%(0603)"))
    )
    (comp (ref "R39")
      (value "100")
      (footprint "eagle-import:0603-RES")
      (libsource (lib "eagle-import") (part "100OHM1/10W1%(0603)"))
    )
    (comp (ref "R40")
      (value "1M")
      (footprint "eagle-import:0603-RES")
      (libsource (lib "eagle-import") (part "100OHM1/10W1%(0603)"))
    )
    (comp (ref "SV1")
      (value "MA07-1")
      (footprint "eagle-import:MA07-1")
      (libsource (lib "eagle-import") (part "MA07-1"))
    )
    (comp (ref "SV2")
      (value "MA03-1")
      (footprint "eagle-import:MA03-1")
      (libsource (lib "eagle-import") (part "MA03-1"))
    )
    (comp (ref "SV3")
      (value "MA04-1")
      (footprint "eagle-import:MA04-1")
      (libsource (lib "eagle-import") (part "MA04-1"))
    )
    (comp (ref "SV4")
      (value "MA03-1")
      (footprint "eagle-import:MA03-1")
      (libsource (lib "eagle-import") (part "MA03-1"))
    )
    (comp (ref "U1")
      (value "ATMEGA328P")
      (footprint "eagle-import:TQFP32-08")
      (libsource (lib "eagle-import") (part "ATMEGA328_SMT"))
    )
    (comp (ref "U3")
      (value "MCP73831")
      (footprint "eagle-import:SOT23-5")
      (libsource (lib "eagle-import") (part "MCP73831"))
    )
    (comp (ref "X2")
      (value "MINI-USB-32005-301")
      (footprint "eagle-import:32005-301")
      (libsource (lib "eagle-import") (part "MINI-USB-32005-301"))
    )
    (comp (ref "Y1")
      (value "CRYSTAL5X3")
      (footprint "eagle-import:CRYSTAL-SMD-5X3")
      (libsource (lib "eagle-import") (part "CRYSTAL5X3"))
    )
  )
  (nets
    (net (code "1") (name "/+5V") (class "Default")
      (node (ref "IC1") (pin "10") (pinfunction "SCL_10") (pintype "input"))
      (node (ref "IC1") (pin "16") (pinfunction "VCC_16") (pintype "power_in"))
      (node (ref "IC2") (pin "10") (pinfunction "SCL_10") (pintype "input"))
      (node (ref "IC2") (pin "16") (pinfunction "VCC_16") (pintype "power_in"))
      (node (ref "IC3") (pin "10") (pinfunction "SCL_10") (pintype "input"))
      (node (ref "IC3") (pin "16") (pinfunction "VCC_16") (pintype "power_in"))
      (node (ref "R21") (pin "2") (pinfunction "2_2") (pintype "passive"))
      (node (ref "R22") (pin "1") (pinfunction "1_1") (pintype "passive"))
      (node (ref "SV1") (pin "7") (pinfunction "7_7") (pintype "passive"))
      (node (ref "SV2") (pin "1") (pinfunction "1_1") (pintype "passive"))
      (node (ref "U1") (pin "18") (pinfunction "AVCC_18") (pintype "bidirectional"))
      (node (ref "U1") (pin "20") (pinfunction "AREF_20") (pintype "bidirectional"))
      (node (ref "U1") (pin "4") (pinfunction "VCC_4") (pintype "bidirectional"))
      (node (ref "U1") (pin "6") (pinfunction "VCC_6") (pintype "bidirectional"))
    )
    (net (code "2") (name "/A0") (class "Default")
      (node (ref "Q1") (pin "1") (pinfunction "G_1") (pintype "passive"))
      (node (ref "R37") (pin "1") (pinfunction "1_1") (pintype "passive"))
    )
    (net (code "3") (name "/A1") (class "Default")
      (node (ref "Q2") (pin "1") (pinfunction "G_1") (pintype "passive"))
      (node (ref "R36") (pin "1") (pinfunction "1_1") (pintype "passive"))
    )
    (net (code "4") (name "/A2") (class "Default")
      (node (ref "Q3") (pin "1") (pinfunction "G_1") (pintype "passive"))
      (node (ref "R39") (pin "1") (pinfunction "1_1") (pintype "passive"))
    )
    (net (code "5") (name "/A3") (class "Default")
      (node (ref "Q6") (pin "1") (pinfunction "G_1") (pintype "passive"))
      (node (ref "R38") (pin "1") (pinfunction "1_1") (pintype "passive"))
    )
    (net (code "6") (name "/A4") (class "Default")
      (node (ref "Q8") (pin "1") (pinfunction "G_1") (pintype "passive"))
      (node (ref "R35") (pin "1") (pinfunction "1_1") (pintype "passive"))
    )
    (net (code "7") (name "/A5") (class "Default")
      (node (ref "Q10") (pin "1") (pinfunction "G_1") (pintype "passive"))
      (node (ref "R34") (pin "1") (pinfunction "1_1") (pintype "passive"))
    )
    (net (code "8") (name "/A6") (class "Default")
      (node (ref "Q12") (pin "1") (pinfunction "G_1") (pintype "passive"))
      (node (ref "R33") (pin "1") (pinfunction "1_1") (pintype "passive"))
    )
    (net (code "9") (name "/A7") (class "Default")
      (node (ref "Q14") (pin "1") (pinfunction "G_1") (pintype "passive"))
      (node (ref "R32") (pin "1") (pinfunction "1_1") (pintype "passive"))
    )
    (net (code "10") (name "/A8") (class "Default")
      (node (ref "Q16") (pin "1") (pinfunction "G_1") (pintype "passive"))
      (node (ref "R31") (pin "1") (pinfunction "1_1") (pintype "passive"))
    )
    (net (code "11") (name "/A9") (class "Default")
      (node (ref "Q19") (pin "1") (pinfunction "G_1") (pintype "passive"))
      (node (ref "R30") (pin "1") (pinfunction "1_1") (pintype "passive"))
    )
    (net (code "12") (name "/BAT+") (class "Default")
      (node (ref "C9") (pin "1") (pinfunction "1_1") (pintype "passive"))
      (node (ref "SV1") (pin "2") (pinfunction "2_2") (pintype "passive"))
      (node (ref "SV4") (pin "2") (pinfunction "2_2") (pintype "passive"))
      (node (ref "U3") (pin "3") (pinfunction "VBAT_3") (pintype "power_in"))
    )
    (net (code "13") (name "/BLANK") (class "Default")
      (node (ref "IC1") (pin "13") (pinfunction "G_13") (pintype "input"))
      (node (ref "IC2") (pin "13") (pinfunction "G_13") (pintype "input"))
      (node (ref "IC3") (pin "13") (pinfunction "G_13") (pintype "input"))
      (node (ref "R22") (pin "2") (pinfunction "2_2") (pintype "passive"))
      (node (ref "U1") (pin "22") (pinfunction "ADC7_22") (pintype "bidirectional"))
    )
    (net (code "14") (name "/CHARGE") (class "Default")
      (node (ref "C8") (pin "1") (pinfunction "1_1") (pintype "passive"))
      (node (ref "LED321") (pin "A") (pinfunction "A_A") (pintype "passive"))
      (node (ref "U3") (pin "4") (pinfunction "VIN_4") (pintype "power_in"))
      (node (ref "X2") (pin "1") (pinfunction "1_1") (pintype "passive"))
    )
    (net (code "15") (name "/CLOCK") (class "Default")
      (node (ref "IC1") (pin "11") (pinfunction "SCK_11") (pintype "input"))
      (node (ref "IC2") (pin "11") (pinfunction "SCK_11") (pintype "input"))
      (node (ref "IC3") (pin "11") (pinfunction "SCK_11") (pintype "input"))
      (node (ref "U1") (pin "17") (pinfunction "PB5(SCK)_17") (pintype "bidirectional"))
    )
    (net (code "16") (name "/D0") (class "Default")
      (node (ref "LED100") (pin "A") (pinfunction "A_A") (pintype "passive"))
      (node (ref "LED120") (pin "A") (pinfunction "A_A") (pintype "passive"))
      (node (ref "LED140") (pin "A") (pinfunction "A_A") (pintype "passive"))
      (node (ref "LED160") (pin "A") (pinfunction "A_A") (pintype "passive"))
      (node (ref "LED180") (pin "A") (pinfunction "A_A") (pintype "passive"))
      (node (ref "LED20") (pin "A") (pinfunction "A_A") (pintype "passive"))
      (node (ref "LED200") (pin "A") (pinfunction "A_A") (pintype "passive"))
      (node (ref "LED40") (pin "A") (pinfunction "A_A") (pintype "passive"))
      (node (ref "LED60") (pin "A") (pinfunction "A_A") (pintype "passive"))
      (node (ref "LED80") (pin "A") (pinfunction "A_A") (pintype "passive"))
      (node (ref "R1") (pin "2") (pinfunction "2_2") (pintype "passive"))
    )
    (net (code "17") (name "/D1") (class "Default")
      (node (ref "LED101") (pin "A") (pinfunction "A_A") (pintype "passive"))
      (node (ref "LED121") (pin "A") (pinfunction "A_A") (pintype "passive"))
      (node (ref "LED141") (pin "A") (pinfunction "A_A") (pintype "passive"))
      (node (ref "LED161") (pin "A") (pinfunction "A_A") (pintype "passive"))
      (node (ref "LED181") (pin "A") (pinfunction "A_A") (pintype "passive"))
      (node (ref "LED2") (pin "A") (pinfunction "A_A") (pintype "passive"))
      (node (ref "LED21") (pin "A") (pinfunction "A_A") (pintype "passive"))
      (node (ref "LED41") (pin "A") (pinfunction "A_A") (pintype "passive"))
      (node (ref "LED61") (pin "A") (pinfunction "A_A") (pintype "passive"))
      (node (ref "LED81") (pin "A") (pinfunction "A_A") (pintype "passive"))
      (node (ref "R2") (pin "2") (pinfunction "2_2") (pintype "passive"))
    )
    (net (code "18") (name "/D2") (class "Default")
      (node (ref "LED102") (pin "A") (pinfunction "A_A") (pintype "passive"))
      (node (ref "LED122") (pin "A") (pinfunction "A_A") (pintype "passive"))
      (node (ref "LED142") (pin "A") (pinfunction "A_A") (pintype "passive"))
      (node (ref "LED162") (pin "A") (pinfunction "A_A") (pintype "passive"))
      (node (ref "LED182") (pin "A") (pinfunction "A_A") (pintype "passive"))
      (node (ref "LED22") (pin "A") (pinfunction "A_A") (pintype "passive"))
      (node (ref "LED3") (pin "A") (pinfunction "A_A") (pintype "passive"))
      (node (ref "LED42") (pin "A") (pinfunction "A_A") (pintype "passive"))
      (node (ref "LED62") (pin "A") (pinfunction "A_A") (pintype "passive"))
      (node (ref "LED82") (pin "A") (pinfunction "A_A") (pintype "passive"))
      (node (ref "R3") (pin "2") (pinfunction "2_2") (pintype "passive"))
    )
    (net (code "19") (name "/D3") (class "Default")
      (node (ref "LED103") (pin "A") (pinfunction "A_A") (pintype "passive"))
      (node (ref "LED123") (pin "A") (pinfunction "A_A") (pintype "passive"))
      (node (ref "LED143") (pin "A") (pinfunction "A_A") (pintype "passive"))
      (node (ref "LED163") (pin "A") (pinfunction "A_A") (pintype "passive"))
      (node (ref "LED183") (pin "A") (pinfunction "A_A") (pintype "passive"))
      (node (ref "LED23") (pin "A") (pinfunction "A_A") (pintype "passive"))
      (node (ref "LED4") (pin "A") (pinfunction "A_A") (pintype "passive"))
      (node (ref "LED43") (pin "A") (pinfunction "A_A") (pintype "passive"))
      (node (ref "LED63") (pin "A") (pinfunction "A_A") (pintype "passive"))
      (node (ref "LED83") (pin "A") (pinfunction "A_A") (pintype "passive"))
      (node (ref "R4") (pin "2") (pinfunction "2_2") (pintype "passive"))
    )
    (net (code "20") (name "/D4") (class "Default")
      (node (ref "LED104") (pin "A") (pinfunction "A_A") (pintype "passive"))
      (node (ref "LED124") (pin "A") (pinfunction "A_A") (pintype "passive"))
      (node (ref "LED144") (pin "A") (pinfunction "A_A") (pintype "passive"))
      (node (ref "LED164") (pin "A") (pinfunction "A_A") (pintype "passive"))
      (node (ref "LED184") (pin "A") (pinfunction "A_A") (pintype "passive"))
      (node (ref "LED24") (pin "A") (pinfunction "A_A") (pintype "passive"))
      (node (ref "LED44") (pin "A") (pinfunction "A_A") (pintype "passive"))
      (node (ref "LED5") (pin "A") (pinfunction "A_A") (pintype "passive"))
      (node (ref "LED64") (pin "A") (pinfunction "A_A") (pintype "passive"))
      (node (ref "LED84") (pin "A") (pinfunction "A_A") (pintype "passive"))
      (node (ref "R5") (pin "2") (pinfunction "2_2") (pintype "passive"))
    )
    (net (code "21") (name "/D5") (class "Default")
      (node (ref "LED105") (pin "A") (pinfunction "A_A") (pintype "passive"))
      (node (ref "LED125") (pin "A") (pinfunction "A_A") (pintype "passive"))
      (node (ref "LED145") (pin "A") (pinfunction "A_A") (pintype "passive"))
      (node (ref "LED165") (pin "A") (pinfunction "A_A") (pintype "passive"))
      (node (ref "LED185") (pin "A") (pinfunction "A_A") (pintype "passive"))
      (node (ref "LED25") (pin "A") (pinfunction "A_A") (pintype "passive"))
      (node (ref "LED45") (pin "A") (pinfunction "A_A") (pintype "passive"))
      (node (ref "LED6") (pin "A") (pinfunction "A_A") (pintype "passive"))
      (node (ref "LED65") (pin "A") (pinfunction "A_A") (pintype "passive"))
      (node (ref "LED85") (pin "A") (pinfunction "A_A") (pintype "passive"))
      (node (ref "R6") (pin "2") (pinfunction "2_2") (pintype "passive"))
    )
    (net (code "22") (name "/D6") (class "Default")
      (node (ref "LED106") (pin "A") (pinfunction "A_A") (pintype "passive"))
      (node (ref "LED126") (pin "A") (pinfunction "A_A") (pintype "passive"))
      (node (ref "LED146") (pin "A") (pinfunction "A_A") (pintype "passive"))
      (node (ref "LED166") (pin "A") (pinfunction "A_A") (pintype "passive"))
      (node (ref "LED186") (pin "A") (pinfunction "A_A") (pintype "passive"))
      (node (ref "LED26") (pin "A") (pinfunction "A_A") (pintype "passive"))
      (node (ref "LED46") (pin "A") (pinfunction "A_A") (pintype "passive"))
      (node (ref "LED66") (pin "A") (pinfunction "A_A") (pintype "passive"))
      (node (ref "LED7") (pin "A") (pinfunction "A_A") (pintype "passive"))
      (node (ref "LED86") (pin "A") (pinfunction "A_A") (pintype "passive"))
      (node (ref "R7") (pin "2") (pinfunction "2_2") (pintype "passive"))
    )
    (net (code "23") (name "/D7") (class "Default")
      (node (ref "LED107") (pin "A") (pinfunction "A_A") (pintype "passive"))
      (node (ref "LED127") (pin "A") (pinfunction "A_A") (pintype "passive"))
      (node (ref "LED147") (pin "A") (pinfunction "A_A") (pintype "passive"))
      (node (ref "LED167") (pin "A") (pinfunction "A_A") (pintype "passive"))
      (node (ref "LED187") (pin "A") (pinfunction "A_A") (pintype "passive"))
      (node (ref "LED27") (pin "A") (pinfunction "A_A") (pintype "passive"))
      (node (ref "LED47") (pin "A") (pinfunction "A_A") (pintype "passive"))
      (node (ref "LED67") (pin "A") (pinfunction "A_A") (pintype "passive"))
      (node (ref "LED8") (pin "A") (pinfunction "A_A") (pintype "passive"))
      (node (ref "LED87") (pin "A") (pinfunction "A_A") (pintype "passive"))
      (node (ref "R8") (pin "2") (pinfunction "2_2") (pintype "passive"))
    )
    (net (code "24") (name "/D8") (class "Default")
      (node (ref "LED108") (pin "A") (pinfunction "A_A") (pintype "passive"))
      (node (ref "LED128") (pin "A") (pinfunction "A_A") (pintype "passive"))
      (node (ref "LED148") (pin "A") (pinfunction "A_A") (pintype "passive"))
      (node (ref "LED168") (pin "A") (pinfunction "A_A") (pintype "passive"))
      (node (ref "LED188") (pin "A") (pinfunction "A_A") (pintype "passive"))
      (node (ref "LED28") (pin "A") (pinfunction "A_A") (pintype "passive"))
      (node (ref "LED48") (pin "A") (pinfunction "A_A") (pintype "passive"))
      (node (ref "LED68") (pin "A") (pinfunction "A_A") (pintype "passive"))
      (node (ref "LED88") (pin "A") (pinfunction "A_A") (pintype "passive"))
      (node (ref "LED9") (pin "A") (pinfunction "A_A") (pintype "passive"))
      (node (ref "R9") (pin "2") (pinfunction "2_2") (pintype "passive"))
    )
    (net (code "25") (name "/D9") (class "Default")
      (node (ref "LED10") (pin "A") (pinfunction "A_A") (pintype "passive"))
      (node (ref "LED109") (pin "A") (pinfunction "A_A") (pintype "passive"))
      (node (ref "LED129") (pin "A") (pinfunction "A_A") (pintype "passive"))
      (node (ref "LED149") (pin "A") (pinfunction "A_A") (pintype "passive"))
      (node (ref "LED169") (pin "A") (pinfunction "A_A") (pintype "passive"))
      (node (ref "LED189") (pin "A") (pinfunction "A_A") (pintype "passive"))
      (node (ref "LED29") (pin "A") (pinfunction "A_A") (pintype "passive"))
      (node (ref "LED49") (pin "A") (pinfunction "A_A") (pintype "passive"))
      (node (ref "LED69") (pin "A") (pinfunction "A_A") (pintype "passive"))
      (node (ref "LED89") (pin "A") (pinfunction "A_A") (pintype "passive"))
      (node (ref "R10") (pin "2") (pinfunction "2_2") (pintype "passive"))
    )
    (net (code "26") (name "/D10") (class "Default")
      (node (ref "LED11") (pin "A") (pinfunction "A_A") (pintype "passive"))
      (node (ref "LED110") (pin "A") (pinfunction "A_A") (pintype "passive"))
      (node (ref "LED130") (pin "A") (pinfunction "A_A") (pintype "passive"))
      (node (ref "LED150") (pin "A") (pinfunction "A_A") (pintype "passive"))
      (node (ref "LED170") (pin "A") (pinfunction "A_A") (pintype "passive"))
      (node (ref "LED190") (pin "A") (pinfunction "A_A") (pintype "passive"))
      (node (ref "LED30") (pin "A") (pinfunction "A_A") (pintype "passive"))
      (node (ref "LED50") (pin "A") (pinfunction "A_A") (pintype "passive"))
      (node (ref "LED70") (pin "A") (pinfunction "A_A") (pintype "passive"))
      (node (ref "LED90") (pin "A") (pinfunction "A_A") (pintype "passive"))
      (node (ref "R11") (pin "2") (pinfunction "2_2") (pintype "passive"))
    )
    (net (code "27") (name "/D11") (class "Default")
      (node (ref "LED111") (pin "A") (pinfunction "A_A") (pintype "passive"))
      (node (ref "LED12") (pin "A") (pinfunction "A_A") (pintype "passive"))
      (node (ref "LED131") (pin "A") (pinfunction "A_A") (pintype "passive"))
      (node (ref "LED151") (pin "A") (pinfunction "A_A") (pintype "passive"))
      (node (ref "LED171") (pin "A") (pinfunction "A_A") (pintype "passive"))
      (node (ref "LED191") (pin "A") (pinfunction "A_A") (pintype "passive"))
      (node (ref "LED31") (pin "A") (pinfunction "A_A") (pintype "passive"))
      (node (ref "LED51") (pin "A") (pinfunction "A_A") (pintype "passive"))
      (node (ref "LED71") (pin "A") (pinfunction "A_A") (pintype "passive"))
      (node (ref "LED91") (pin "A") (pinfunction "A_A") (pintype "passive"))
      (node (ref "R12") (pin "2") (pinfunction "2_2") (pintype "passive"))
    )
    (net (code "28") (name "/D12") (class "Default")
      (node (ref "LED112") (pin "A") (pinfunction "A_A") (pintype "passive"))
      (node (ref "LED13") (pin "A") (pinfunction "A_A") (pintype "passive"))
      (node (ref "LED132") (pin "A") (pinfunction "A_A") (pintype "passive"))
      (node (ref "LED152") (pin "A") (pinfunction "A_A") (pintype "passive"))
      (node (ref "LED172") (pin "A") (pinfunction "A_A") (pintype "passive"))
      (node (ref "LED192") (pin "A") (pinfunction "A_A") (pintype "passive"))
      (node (ref "LED32") (pin "A") (pinfunction "A_A") (pintype "passive"))
      (node (ref "LED52") (pin "A") (pinfunction "A_A") (pintype "passive"))
      (node (ref "LED72") (pin "A") (pinfunction "A_A") (pintype "passive"))
      (node (ref "LED92") (pin "A") (pinfunction "A_A") (pintype "passive"))
      (node (ref "R13") (pin "2") (pinfunction "2_2") (pintype "passive"))
    )
    (net (code "29") (name "/D13") (class "Default")
      (node (ref "LED113") (pin "A") (pinfunction "A_A") (pintype "passive"))
      (node (ref "LED133") (pin "A") (pinfunction "A_A") (pintype "passive"))
      (node (ref "LED14") (pin "A") (pinfunction "A_A") (pintype "passive"))
      (node (ref "LED153") (pin "A") (pinfunction "A_A") (pintype "passive"))
      (node (ref "LED173") (pin "A") (pinfunction "A_A") (pintype "passive"))
      (node (ref "LED193") (pin "A") (pinfunction "A_A") (pintype "passive"))
      (node (ref "LED33") (pin "A") (pinfunction "A_A") (pintype "passive"))
      (node (ref "LED53") (pin "A") (pinfunction "A_A") (pintype "passive"))
      (node (ref "LED73") (pin "A") (pinfunction "A_A") (pintype "passive"))
      (node (ref "LED93") (pin "A") (pinfunction "A_A") (pintype "passive"))
      (node (ref "R14") (pin "2") (pinfunction "2_2") (pintype "passive"))
    )
    (net (code "30") (name "/D14") (class "Default")
      (node (ref "LED114") (pin "A") (pinfunction "A_A") (pintype "passive"))
      (node (ref "LED134") (pin "A") (pinfunction "A_A") (pintype "passive"))
      (node (ref "LED15") (pin "A") (pinfunction "A_A") (pintype "passive"))
      (node (ref "LED154") (pin "A") (pinfunction "A_A") (pintype "passive"))
      (node (ref "LED174") (pin "A") (pinfunction "A_A") (pintype "passive"))
      (node (ref "LED194") (pin "A") (pinfunction "A_A") (pintype "passive"))
      (node (ref "LED34") (pin "A") (pinfunction "A_A") (pintype "passive"))
      (node (ref "LED54") (pin "A") (pinfunction "A_A") (pintype "passive"))
      (node (ref "LED74") (pin "A") (pinfunction "A_A") (pintype "passive"))
      (node (ref "LED94") (pin "A") (pinfunction "A_A") (pintype "passive"))
      (node (ref "R15") (pin "2") (pinfunction "2_2") (pintype "passive"))
    )
    (net (code "31") (name "/D15") (class "Default")
      (node (ref "LED115") (pin "A") (pinfunction "A_A") (pintype "passive"))
      (node (ref "LED135") (pin "A") (pinfunction "A_A") (pintype "passive"))
      (node (ref "LED155") (pin "A") (pinfunction "A_A") (pintype "passive"))
      (node (ref "LED16") (pin "A") (pinfunction "A_A") (pintype "passive"))
      (node (ref "LED175") (pin "A") (pinfunction "A_A") (pintype "passive"))
      (node (ref "LED195") (pin "A") (pinfunction "A_A") (pintype "passive"))
      (node (ref "LED35") (pin "A") (pinfunction "A_A") (pintype "passive"))
      (node (ref "LED55") (pin "A") (pinfunction "A_A") (pintype "passive"))
      (node (ref "LED75") (pin "A") (pinfunction "A_A") (pintype "passive"))
      (node (ref "LED95") (pin "A") (pinfunction "A_A") (pintype "passive"))
      (node (ref "R16") (pin "2") (pinfunction "2_2") (pintype "passive"))
    )
    (net (code "32") (name "/D16") (class "Default")
      (node (ref "LED116") (pin "A") (pinfunction "A_A") (pintype "passive"))
      (node (ref "LED136") (pin "A") (pinfunction "A_A") (pintype "passive"))
      (node (ref "LED156") (pin "A") (pinfunction "A_A") (pintype "passive"))
      (node (ref "LED17") (pin "A") (pinfunction "A_A") (pintype "passive"))
      (node (ref "LED176") (pin "A") (pinfunction "A_A") (pintype "passive"))
      (node (ref "LED196") (pin "A") (pinfunction "A_A") (pintype "passive"))
      (node (ref "LED36") (pin "A") (pinfunction "A_A") (pintype "passive"))
      (node (ref "LED56") (pin "A") (pinfunction "A_A") (pintype "passive"))
      (node (ref "LED76") (pin "A") (pinfunction "A_A") (pintype "passive"))
      (node (ref "LED96") (pin "A") (pinfunction "A_A") (pintype "passive"))
      (node (ref "R17") (pin "2") (pinfunction "2_2") (pintype "passive"))
    )
    (net (code "33") (name "/D17") (class "Default")
      (node (ref "LED117") (pin "A") (pinfunction "A_A") (pintype "passive"))
      (node (ref "LED137") (pin "A") (pinfunction "A_A") (pintype "passive"))
      (node (ref "LED157") (pin "A") (pinfunction "A_A") (pintype "passive"))
      (node (ref "LED177") (pin "A") (pinfunction "A_A") (pintype "passive"))
      (node (ref "LED18") (pin "A") (pinfunction "A_A") (pintype "passive"))
      (node (ref "LED197") (pin "A") (pinfunction "A_A") (pintype "passive"))
      (node (ref "LED37") (pin "A") (pinfunction "A_A") (pintype "passive"))
      (node (ref "LED57") (pin "A") (pinfunction "A_A") (pintype "passive"))
      (node (ref "LED77") (pin "A") (pinfunction "A_A") (pintype "passive"))
      (node (ref "LED97") (pin "A") (pinfunction "A_A") (pintype "passive"))
      (node (ref "R18") (pin "2") (pinfunction "2_2") (pintype "passive"))
    )
    (net (code "34") (name "/D18") (class "Default")
      (node (ref "LED118") (pin "A") (pinfunction "A_A") (pintype "passive"))
      (node (ref "LED138") (pin "A") (pinfunction "A_A") (pintype "passive"))
      (node (ref "LED158") (pin "A") (pinfunction "A_A") (pintype "passive"))
      (node (ref "LED178") (pin "A") (pinfunction "A_A") (pintype "passive"))
      (node (ref "LED19") (pin "A") (pinfunction "A_A") (pintype "passive"))
      (node (ref "LED198") (pin "A") (pinfunction "A_A") (pintype "passive"))
      (node (ref "LED38") (pin "A") (pinfunction "A_A") (pintype "passive"))
      (node (ref "LED58") (pin "A") (pinfunction "A_A") (pintype "passive"))
      (node (ref "LED78") (pin "A") (pinfunction "A_A") (pintype "passive"))
      (node (ref "LED98") (pin "A") (pinfunction "A_A") (pintype "passive"))
      (node (ref "R19") (pin "2") (pinfunction "2_2") (pintype "passive"))
    )
    (net (code "35") (name "/D19") (class "Default")
      (node (ref "LED1") (pin "A") (pinfunction "A_A") (pintype "passive"))
      (node (ref "LED119") (pin "A") (pinfunction "A_A") (pintype "passive"))
      (node (ref "LED139") (pin "A") (pinfunction "A_A") (pintype "passive"))
      (node (ref "LED159") (pin "A") (pinfunction "A_A") (pintype "passive"))
      (node (ref "LED179") (pin "A") (pinfunction "A_A") (pintype "passive"))
      (node (ref "LED199") (pin "A") (pinfunction "A_A") (pintype "passive"))
      (node (ref "LED39") (pin "A") (pinfunction "A_A") (pintype "passive"))
      (node (ref "LED59") (pin "A") (pinfunction "A_A") (pintype "passive"))
      (node (ref "LED79") (pin "A") (pinfunction "A_A") (pintype "passive"))
      (node (ref "LED99") (pin "A") (pinfunction "A_A") (pintype "passive"))
      (node (ref "R20") (pin "2") (pinfunction "2_2") (pintype "passive"))
    )
    (net (code "36") (name "/DATA") (class "Default")
      (node (ref "IC1") (pin "14") (pinfunction "SER_14") (pintype "input"))
      (node (ref "U1") (pin "15") (pinfunction "PB3(MOSI/OC2)_15") (pintype "bidirectional"))
    )
    (net (code "38") (name "/GND") (class "Default")
      (node (ref "2K") (pin "2") (pinfunction "2_2") (pintype "passive"))
      (node (ref "C2") (pin "1") (pinfunction "1_1") (pintype "passive"))
      (node (ref "C3") (pin "1") (pinfunction "1_1") (pintype "passive"))
      (node (ref "C4") (pin "2") (pinfunction "2_2") (pintype "passive"))
      (node (ref "C5") (pin "2") (pinfunction "2_2") (pintype "passive"))
      (node (ref "C6") (pin "2") (pinfunction "2_2") (pintype "passive"))
      (node (ref "C7") (pin "2") (pinfunction "2_2") (pintype "passive"))
      (node (ref "C8") (pin "2") (pinfunction "2_2") (pintype "passive"))
      (node (ref "C9") (pin "2") (pinfunction "2_2") (pintype "passive"))
      (node (ref "IC1") (pin "8") (pinfunction "GND_8") (pintype "power_in"))
      (node (ref "IC2") (pin "8") (pinfunction "GND_8") (pintype "power_in"))
      (node (ref "IC3") (pin "8") (pinfunction "GND_8") (pintype "power_in"))
      (node (ref "Q1") (pin "2") (pinfunction "S_2") (pintype "passive"))
      (node (ref "Q10") (pin "2") (pinfunction "S_2") (pintype "passive"))
      (node (ref "Q12") (pin "2") (pinfunction "S_2") (pintype "passive"))
      (node (ref "Q14") (pin "2") (pinfunction "S_2") (pintype "passive"))
      (node (ref "Q16") (pin "2") (pinfunction "S_2") (pintype "passive"))
      (node (ref "Q19") (pin "2") (pinfunction "S_2") (pintype "passive"))
      (node (ref "Q2") (pin "2") (pinfunction "S_2") (pintype "passive"))
      (node (ref "Q3") (pin "2") (pinfunction "S_2") (pintype "passive"))
      (node (ref "Q6") (pin "2") (pinfunction "S_2") (pintype "passive"))
      (node (ref "Q8") (pin "2") (pinfunction "S_2") (pintype "passive"))
      (node (ref "SV1") (pin "1") (pinfunction "1_1") (pintype "passive"))
      (node (ref "SV1") (pin "6") (pinfunction "6_6") (pintype "passive"))
      (node (ref "SV2") (pin "2") (pinfunction "2_2") (pintype "passive"))
      (node (ref "U1") (pin "21") (pinfunction "AGND_21") (pintype "bidirectional"))
      (node (ref "U1") (pin "3") (pinfunction "GND_3") (pintype "bidirectional"))
      (node (ref "U1") (pin "5") (pinfunction "GND_5") (pintype "bidirectional"))
      (node (ref "U3") (pin "2") (pinfunction "VSS_2") (pintype "power_in"))
      (node (ref "X2") (pin "5") (pinfunction "5_5") (pintype "passive"))
    )
    (net (code "39") (name "/LATCH") (class "Default")
      (node (ref "IC1") (pin "12") (pinfunction "RCK_12") (pintype "input"))
      (node (ref "IC2") (pin "12") (pinfunction "RCK_12") (pintype "input"))
      (node (ref "IC3") (pin "12") (pinfunction "RCK_12") (pintype "input"))
      (node (ref "U1") (pin "32") (pinfunction "PD2(INT0)_32") (pintype "bidirectional"))
    )
    (net (code "40") (name "/RST") (class "Default")
      (node (ref "C1") (pin "1") (pinfunction "1_1") (pintype "passive"))
      (node (ref "SV1") (pin "3") (pinfunction "3_3") (pintype "passive"))
    )
    (net (code "41") (name "/RX") (class "Default")
      (node (ref "R38") (pin "2") (pinfunction "2_2") (pintype "passive"))
      (node (ref "SV1") (pin "5") (pinfunction "5_5") (pintype "passive"))
      (node (ref "U1") (pin "30") (pinfunction "PD0(RXD)_30") (pintype "bidirectional"))
    )
    (net (code "42") (name "/TOUCH1") (class "Default")
      (node (ref "C4") (pin "1") (pinfunction "1_1") (pintype "passive"))
      (node (ref "R26") (pin "1") (pinfunction "1_1") (pintype "passive"))
      (node (ref "SV3") (pin "4") (pinfunction "4_4") (pintype "passive"))
      (node (ref "U1") (pin "19") (pinfunction "ADC6_19") (pintype "bidirectional"))
    )
    (net (code "43") (name "/TOUCH2") (class "Default")
      (node (ref "C5") (pin "1") (pinfunction "1_1") (pintype "passive"))
      (node (ref "R24") (pin "1") (pinfunction "1_1") (pintype "passive"))
      (node (ref "SV3") (pin "3") (pinfunction "3_3") (pintype "passive"))
      (node (ref "U1") (pin "14") (pinfunction "PB2(SS/OC1B)_14") (pintype "bidirectional"))
    )
    (net (code "44") (name "/TOUCH3") (class "Default")
      (node (ref "C7") (pin "1") (pinfunction "1_1") (pintype "passive"))
      (node (ref "R23") (pin "1") (pinfunction "1_1") (pintype "passive"))
      (node (ref "SV3") (pin "1") (pinfunction "1_1") (pintype "passive"))
      (node (ref "U1") (pin "10") (pinfunction "PD6(AIN0)_10") (pintype "bidirectional"))
    )
    (net (code "45") (name "/TOUCH4") (class "Default")
      (node (ref "C6") (pin "1") (pinfunction "1_1") (pintype "passive"))
      (node (ref "R40") (pin "1") (pinfunction "1_1") (pintype "passive"))
      (node (ref "SV3") (pin "2") (pinfunction "2_2") (pintype "passive"))
      (node (ref "U1") (pin "12") (pinfunction "PB0(ICP)_12") (pintype "bidirectional"))
    )
    (net (code "46") (name "/TX") (class "Default")
      (node (ref "R39") (pin "2") (pinfunction "2_2") (pintype "passive"))
      (node (ref "SV1") (pin "4") (pinfunction "4_4") (pintype "passive"))
      (node (ref "U1") (pin "31") (pinfunction "PD1(TXD)_31") (pintype "bidirectional"))
    )
    (net (code "47") (name "Net-(470R-Pad1)") (class "Default")
      (node (ref "470R") (pin "1") (pinfunction "1_1") (pintype "passive"))
      (node (ref "LED321") (pin "C") (pinfunction "C_C") (pintype "passive"))
    )
    (net (code "48") (name "Net-(IC1-QB)") (class "Default")
      (node (ref "IC1") (pin "1") (pinfunction "QB_1") (pintype "tri_state"))
      (node (ref "R2") (pin "1") (pinfunction "1_1") (pintype "passive"))
    )
    (net (code "49") (name "Net-(IC1-QC)") (class "Default")
      (node (ref "IC1") (pin "2") (pinfunction "QC_2") (pintype "tri_state"))
      (node (ref "R3") (pin "1") (pinfunction "1_1") (pintype "passive"))
    )
    (net (code "50") (name "Net-(IC1-QD)") (class "Default")
      (node (ref "IC1") (pin "3") (pinfunction "QD_3") (pintype "tri_state"))
      (node (ref "R4") (pin "1") (pinfunction "1_1") (pintype "passive"))
    )
    (net (code "51") (name "Net-(IC1-QE)") (class "Default")
      (node (ref "IC1") (pin "4") (pinfunction "QE_4") (pintype "tri_state"))
      (node (ref "R5") (pin "1") (pinfunction "1_1") (pintype "passive"))
    )
    (net (code "52") (name "Net-(IC1-QF)") (class "Default")
      (node (ref "IC1") (pin "5") (pinfunction "QF_5") (pintype "tri_state"))
      (node (ref "R6") (pin "1") (pinfunction "1_1") (pintype "passive"))
    )
    (net (code "53") (name "Net-(IC1-QG)") (class "Default")
      (node (ref "IC1") (pin "6") (pinfunction "QG_6") (pintype "tri_state"))
      (node (ref "R7") (pin "1") (pinfunction "1_1") (pintype "passive"))
    )
    (net (code "54") (name "Net-(IC1-QH)") (class "Default")
      (node (ref "IC1") (pin "7") (pinfunction "QH_7") (pintype "tri_state"))
      (node (ref "R8") (pin "1") (pinfunction "1_1") (pintype "passive"))
    )
    (net (code "55") (name "Net-(IC1-QH*)") (class "Default")
      (node (ref "IC1") (pin "9") (pinfunction "QH*_9") (pintype "tri_state"))
      (node (ref "IC2") (pin "14") (pinfunction "SER_14") (pintype "input"))
    )
    (net (code "56") (name "Net-(IC2-QA)") (class "Default")
      (node (ref "IC2") (pin "15") (pinfunction "QA_15") (pintype "tri_state"))
      (node (ref "R9") (pin "1") (pinfunction "1_1") (pintype "passive"))
    )
    (net (code "57") (name "Net-(IC2-QB)") (class "Default")
      (node (ref "IC2") (pin "1") (pinfunction "QB_1") (pintype "tri_state"))
      (node (ref "R10") (pin "1") (pinfunction "1_1") (pintype "passive"))
    )
    (net (code "58") (name "Net-(IC2-QC)") (class "Default")
      (node (ref "IC2") (pin "2") (pinfunction "QC_2") (pintype "tri_state"))
      (node (ref "R11") (pin "1") (pinfunction "1_1") (pintype "passive"))
    )
    (net (code "59") (name "Net-(IC2-QD)") (class "Default")
      (node (ref "IC2") (pin "3") (pinfunction "QD_3") (pintype "tri_state"))
      (node (ref "R12") (pin "1") (pinfunction "1_1") (pintype "passive"))
    )
    (net (code "60") (name "Net-(IC2-QE)") (class "Default")
      (node (ref "IC2") (pin "4") (pinfunction "QE_4") (pintype "tri_state"))
      (node (ref "R13") (pin "1") (pinfunction "1_1") (pintype "passive"))
    )
    (net (code "61") (name "Net-(IC2-QF)") (class "Default")
      (node (ref "IC2") (pin "5") (pinfunction "QF_5") (pintype "tri_state"))
      (node (ref "R14") (pin "1") (pinfunction "1_1") (pintype "passive"))
    )
    (net (code "62") (name "Net-(IC2-QG)") (class "Default")
      (node (ref "IC2") (pin "6") (pinfunction "QG_6") (pintype "tri_state"))
      (node (ref "R15") (pin "1") (pinfunction "1_1") (pintype "passive"))
    )
    (net (code "63") (name "Net-(IC2-QH)") (class "Default")
      (node (ref "IC2") (pin "7") (pinfunction "QH_7") (pintype "tri_state"))
      (node (ref "R16") (pin "1") (pinfunction "1_1") (pintype "passive"))
    )
    (net (code "64") (name "Net-(IC2-QH*)") (class "Default")
      (node (ref "IC2") (pin "9") (pinfunction "QH*_9") (pintype "tri_state"))
      (node (ref "IC3") (pin "14") (pinfunction "SER_14") (pintype "input"))
    )
    (net (code "65") (name "Net-(IC3-QB)") (class "Default")
      (node (ref "IC3") (pin "1") (pinfunction "QB_1") (pintype "tri_state"))
      (node (ref "R17") (pin "1") (pinfunction "1_1") (pintype "passive"))
    )
    (net (code "66") (name "Net-(IC3-QC)") (class "Default")
      (node (ref "IC3") (pin "2") (pinfunction "QC_2") (pintype "tri_state"))
      (node (ref "R18") (pin "1") (pinfunction "1_1") (pintype "passive"))
    )
    (net (code "67") (name "Net-(IC3-QD)") (class "Default")
      (node (ref "IC3") (pin "3") (pinfunction "QD_3") (pintype "tri_state"))
      (node (ref "R19") (pin "1") (pinfunction "1_1") (pintype "passive"))
    )
    (net (code "68") (name "Net-(IC3-QE)") (class "Default")
      (node (ref "IC3") (pin "4") (pinfunction "QE_4") (pintype "tri_state"))
      (node (ref "R20") (pin "1") (pinfunction "1_1") (pintype "passive"))
    )
    (net (code "69") (name "Net-(IC3-QF)") (class "Default")
      (node (ref "IC3") (pin "5") (pinfunction "QF_5") (pintype "tri_state"))
      (node (ref "R1") (pin "1") (pinfunction "1_1") (pintype "passive"))
    )
    (net (code "70") (name "Net-(Q1-D)") (class "Default")
      (node (ref "LED1") (pin "C") (pinfunction "C_C") (pintype "passive"))
      (node (ref "LED10") (pin "C") (pinfunction "C_C") (pintype "passive"))
      (node (ref "LED11") (pin "C") (pinfunction "C_C") (pintype "passive"))
      (node (ref "LED12") (pin "C") (pinfunction "C_C") (pintype "passive"))
      (node (ref "LED13") (pin "C") (pinfunction "C_C") (pintype "passive"))
      (node (ref "LED14") (pin "C") (pinfunction "C_C") (pintype "passive"))
      (node (ref "LED15") (pin "C") (pinfunction "C_C") (pintype "passive"))
      (node (ref "LED16") (pin "C") (pinfunction "C_C") (pintype "passive"))
      (node (ref "LED17") (pin "C") (pinfunction "C_C") (pintype "passive"))
      (node (ref "LED18") (pin "C") (pinfunction "C_C") (pintype "passive"))
      (node (ref "LED19") (pin "C") (pinfunction "C_C") (pintype "passive"))
      (node (ref "LED2") (pin "C") (pinfunction "C_C") (pintype "passive"))
      (node (ref "LED20") (pin "C") (pinfunction "C_C") (pintype "passive"))
      (node (ref "LED3") (pin "C") (pinfunction "C_C") (pintype "passive"))
      (node (ref "LED4") (pin "C") (pinfunction "C_C") (pintype "passive"))
      (node (ref "LED5") (pin "C") (pinfunction "C_C") (pintype "passive"))
      (node (ref "LED6") (pin "C") (pinfunction "C_C") (pintype "passive"))
      (node (ref "LED7") (pin "C") (pinfunction "C_C") (pintype "passive"))
      (node (ref "LED8") (pin "C") (pinfunction "C_C") (pintype "passive"))
      (node (ref "LED9") (pin "C") (pinfunction "C_C") (pintype "passive"))
      (node (ref "Q1") (pin "3") (pinfunction "D_3") (pintype "passive"))
    )
    (net (code "71") (name "Net-(Q2-D)") (class "Default")
      (node (ref "LED21") (pin "C") (pinfunction "C_C") (pintype "passive"))
      (node (ref "LED22") (pin "C") (pinfunction "C_C") (pintype "passive"))
      (node (ref "LED23") (pin "C") (pinfunction "C_C") (pintype "passive"))
      (node (ref "LED24") (pin "C") (pinfunction "C_C") (pintype "passive"))
      (node (ref "LED25") (pin "C") (pinfunction "C_C") (pintype "passive"))
      (node (ref "LED26") (pin "C") (pinfunction "C_C") (pintype "passive"))
      (node (ref "LED27") (pin "C") (pinfunction "C_C") (pintype "passive"))
      (node (ref "LED28") (pin "C") (pinfunction "C_C") (pintype "passive"))
      (node (ref "LED29") (pin "C") (pinfunction "C_C") (pintype "passive"))
      (node (ref "LED30") (pin "C") (pinfunction "C_C") (pintype "passive"))
      (node (ref "LED31") (pin "C") (pinfunction "C_C") (pintype "passive"))
      (node (ref "LED32") (pin "C") (pinfunction "C_C") (pintype "passive"))
      (node (ref "LED33") (pin "C") (pinfunction "C_C") (pintype "passive"))
      (node (ref "LED34") (pin "C") (pinfunction "C_C") (pintype "passive"))
      (node (ref "LED35") (pin "C") (pinfunction "C_C") (pintype "passive"))
      (node (ref "LED36") (pin "C") (pinfunction "C_C") (pintype "passive"))
      (node (ref "LED37") (pin "C") (pinfunction "C_C") (pintype "passive"))
      (node (ref "LED38") (pin "C") (pinfunction "C_C") (pintype "passive"))
      (node (ref "LED39") (pin "C") (pinfunction "C_C") (pintype "passive"))
      (node (ref "LED40") (pin "C") (pinfunction "C_C") (pintype "passive"))
      (node (ref "Q2") (pin "3") (pinfunction "D_3") (pintype "passive"))
    )
    (net (code "72") (name "Net-(Q3-D)") (class "Default")
      (node (ref "LED41") (pin "C") (pinfunction "C_C") (pintype "passive"))
      (node (ref "LED42") (pin "C") (pinfunction "C_C") (pintype "passive"))
      (node (ref "LED43") (pin "C") (pinfunction "C_C") (pintype "passive"))
      (node (ref "LED44") (pin "C") (pinfunction "C_C") (pintype "passive"))
      (node (ref "LED45") (pin "C") (pinfunction "C_C") (pintype "passive"))
      (node (ref "LED46") (pin "C") (pinfunction "C_C") (pintype "passive"))
      (node (ref "LED47") (pin "C") (pinfunction "C_C") (pintype "passive"))
      (node (ref "LED48") (pin "C") (pinfunction "C_C") (pintype "passive"))
      (node (ref "LED49") (pin "C") (pinfunction "C_C") (pintype "passive"))
      (node (ref "LED50") (pin "C") (pinfunction "C_C") (pintype "passive"))
      (node (ref "LED51") (pin "C") (pinfunction "C_C") (pintype "passive"))
      (node (ref "LED52") (pin "C") (pinfunction "C_C") (pintype "passive"))
      (node (ref "LED53") (pin "C") (pinfunction "C_C") (pintype "passive"))
      (node (ref "LED54") (pin "C") (pinfunction "C_C") (pintype "passive"))
      (node (ref "LED55") (pin "C") (pinfunction "C_C") (pintype "passive"))
      (node (ref "LED56") (pin "C") (pinfunction "C_C") (pintype "passive"))
      (node (ref "LED57") (pin "C") (pinfunction "C_C") (pintype "passive"))
      (node (ref "LED58") (pin "C") (pinfunction "C_C") (pintype "passive"))
      (node (ref "LED59") (pin "C") (pinfunction "C_C") (pintype "passive"))
      (node (ref "LED60") (pin "C") (pinfunction "C_C") (pintype "passive"))
      (node (ref "Q3") (pin "3") (pinfunction "D_3") (pintype "passive"))
    )
    (net (code "73") (name "Net-(Q6-D)") (class "Default")
      (node (ref "LED61") (pin "C") (pinfunction "C_C") (pintype "passive"))
      (node (ref "LED62") (pin "C") (pinfunction "C_C") (pintype "passive"))
      (node (ref "LED63") (pin "C") (pinfunction "C_C") (pintype "passive"))
      (node (ref "LED64") (pin "C") (pinfunction "C_C") (pintype "passive"))
      (node (ref "LED65") (pin "C") (pinfunction "C_C") (pintype "passive"))
      (node (ref "LED66") (pin "C") (pinfunction "C_C") (pintype "passive"))
      (node (ref "LED67") (pin "C") (pinfunction "C_C") (pintype "passive"))
      (node (ref "LED68") (pin "C") (pinfunction "C_C") (pintype "passive"))
      (node (ref "LED69") (pin "C") (pinfunction "C_C") (pintype "passive"))
      (node (ref "LED70") (pin "C") (pinfunction "C_C") (pintype "passive"))
      (node (ref "LED71") (pin "C") (pinfunction "C_C") (pintype "passive"))
      (node (ref "LED72") (pin "C") (pinfunction "C_C") (pintype "passive"))
      (node (ref "LED73") (pin "C") (pinfunction "C_C") (pintype "passive"))
      (node (ref "LED74") (pin "C") (pinfunction "C_C") (pintype "passive"))
      (node (ref "LED75") (pin "C") (pinfunction "C_C") (pintype "passive"))
      (node (ref "LED76") (pin "C") (pinfunction "C_C") (pintype "passive"))
      (node (ref "LED77") (pin "C") (pinfunction "C_C") (pintype "passive"))
      (node (ref "LED78") (pin "C") (pinfunction "C_C") (pintype "passive"))
      (node (ref "LED79") (pin "C") (pinfunction "C_C") (pintype "passive"))
      (node (ref "LED80") (pin "C") (pinfunction "C_C") (pintype "passive"))
      (node (ref "Q6") (pin "3") (pinfunction "D_3") (pintype "passive"))
    )
    (net (code "74") (name "Net-(Q8-D)") (class "Default")
      (node (ref "LED100") (pin "C") (pinfunction "C_C") (pintype "passive"))
      (node (ref "LED81") (pin "C") (pinfunction "C_C") (pintype "passive"))
      (node (ref "LED82") (pin "C") (pinfunction "C_C") (pintype "passive"))
      (node (ref "LED83") (pin "C") (pinfunction "C_C") (pintype "passive"))
      (node (ref "LED84") (pin "C") (pinfunction "C_C") (pintype "passive"))
      (node (ref "LED85") (pin "C") (pinfunction "C_C") (pintype "passive"))
      (node (ref "LED86") (pin "C") (pinfunction "C_C") (pintype "passive"))
      (node (ref "LED87") (pin "C") (pinfunction "C_C") (pintype "passive"))
      (node (ref "LED88") (pin "C") (pinfunction "C_C") (pintype "passive"))
      (node (ref "LED89") (pin "C") (pinfunction "C_C") (pintype "passive"))
      (node (ref "LED90") (pin "C") (pinfunction "C_C") (pintype "passive"))
      (node (ref "LED91") (pin "C") (pinfunction "C_C") (pintype "passive"))
      (node (ref "LED92") (pin "C") (pinfunction "C_C") (pintype "passive"))
      (node (ref "LED93") (pin "C") (pinfunction "C_C") (pintype "passive"))
      (node (ref "LED94") (pin "C") (pinfunction "C_C") (pintype "passive"))
      (node (ref "LED95") (pin "C") (pinfunction "C_C") (pintype "passive"))
      (node (ref "LED96") (pin "C") (pinfunction "C_C") (pintype "passive"))
      (node (ref "LED97") (pin "C") (pinfunction "C_C") (pintype "passive"))
      (node (ref "LED98") (pin "C") (pinfunction "C_C") (pintype "passive"))
      (node (ref "LED99") (pin "C") (pinfunction "C_C") (pintype "passive"))
      (node (ref "Q8") (pin "3") (pinfunction "D_3") (pintype "passive"))
    )
    (net (code "75") (name "Net-(Q10-D)") (class "Default")
      (node (ref "LED101") (pin "C") (pinfunction "C_C") (pintype "passive"))
      (node (ref "LED102") (pin "C") (pinfunction "C_C") (pintype "passive"))
      (node (ref "LED103") (pin "C") (pinfunction "C_C") (pintype "passive"))
      (node (ref "LED104") (pin "C") (pinfunction "C_C") (pintype "passive"))
      (node (ref "LED105") (pin "C") (pinfunction "C_C") (pintype "passive"))
      (node (ref "LED106") (pin "C") (pinfunction "C_C") (pintype "passive"))
      (node (ref "LED107") (pin "C") (pinfunction "C_C") (pintype "passive"))
      (node (ref "LED108") (pin "C") (pinfunction "C_C") (pintype "passive"))
      (node (ref "LED109") (pin "C") (pinfunction "C_C") (pintype "passive"))
      (node (ref "LED110") (pin "C") (pinfunction "C_C") (pintype "passive"))
      (node (ref "LED111") (pin "C") (pinfunction "C_C") (pintype "passive"))
      (node (ref "LED112") (pin "C") (pinfunction "C_C") (pintype "passive"))
      (node (ref "LED113") (pin "C") (pinfunction "C_C") (pintype "passive"))
      (node (ref "LED114") (pin "C") (pinfunction "C_C") (pintype "passive"))
      (node (ref "LED115") (pin "C") (pinfunction "C_C") (pintype "passive"))
      (node (ref "LED116") (pin "C") (pinfunction "C_C") (pintype "passive"))
      (node (ref "LED117") (pin "C") (pinfunction "C_C") (pintype "passive"))
      (node (ref "LED118") (pin "C") (pinfunction "C_C") (pintype "passive"))
      (node (ref "LED119") (pin "C") (pinfunction "C_C") (pintype "passive"))
      (node (ref "LED120") (pin "C") (pinfunction "C_C") (pintype "passive"))
      (node (ref "Q10") (pin "3") (pinfunction "D_3") (pintype "passive"))
    )
    (net (code "76") (name "Net-(Q12-D)") (class "Default")
      (node (ref "LED121") (pin "C") (pinfunction "C_C") (pintype "passive"))
      (node (ref "LED122") (pin "C") (pinfunction "C_C") (pintype "passive"))
      (node (ref "LED123") (pin "C") (pinfunction "C_C") (pintype "passive"))
      (node (ref "LED124") (pin "C") (pinfunction "C_C") (pintype "passive"))
      (node (ref "LED125") (pin "C") (pinfunction "C_C") (pintype "passive"))
      (node (ref "LED126") (pin "C") (pinfunction "C_C") (pintype "passive"))
      (node (ref "LED127") (pin "C") (pinfunction "C_C") (pintype "passive"))
      (node (ref "LED128") (pin "C") (pinfunction "C_C") (pintype "passive"))
      (node (ref "LED129") (pin "C") (pinfunction "C_C") (pintype "passive"))
      (node (ref "LED130") (pin "C") (pinfunction "C_C") (pintype "passive"))
      (node (ref "LED131") (pin "C") (pinfunction "C_C") (pintype "passive"))
      (node (ref "LED132") (pin "C") (pinfunction "C_C") (pintype "passive"))
      (node (ref "LED133") (pin "C") (pinfunction "C_C") (pintype "passive"))
      (node (ref "LED134") (pin "C") (pinfunction "C_C") (pintype "passive"))
      (node (ref "LED135") (pin "C") (pinfunction "C_C") (pintype "passive"))
      (node (ref "LED136") (pin "C") (pinfunction "C_C") (pintype "passive"))
      (node (ref "LED137") (pin "C") (pinfunction "C_C") (pintype "passive"))
      (node (ref "LED138") (pin "C") (pinfunction "C_C") (pintype "passive"))
      (node (ref "LED139") (pin "C") (pinfunction "C_C") (pintype "passive"))
      (node (ref "LED140") (pin "C") (pinfunction "C_C") (pintype "passive"))
      (node (ref "Q12") (pin "3") (pinfunction "D_3") (pintype "passive"))
    )
    (net (code "77") (name "Net-(Q14-D)") (class "Default")
      (node (ref "LED141") (pin "C") (pinfunction "C_C") (pintype "passive"))
      (node (ref "LED142") (pin "C") (pinfunction "C_C") (pintype "passive"))
      (node (ref "LED143") (pin "C") (pinfunction "C_C") (pintype "passive"))
      (node (ref "LED144") (pin "C") (pinfunction "C_C") (pintype "passive"))
      (node (ref "LED145") (pin "C") (pinfunction "C_C") (pintype "passive"))
      (node (ref "LED146") (pin "C") (pinfunction "C_C") (pintype "passive"))
      (node (ref "LED147") (pin "C") (pinfunction "C_C") (pintype "passive"))
      (node (ref "LED148") (pin "C") (pinfunction "C_C") (pintype "passive"))
      (node (ref "LED149") (pin "C") (pinfunction "C_C") (pintype "passive"))
      (node (ref "LED150") (pin "C") (pinfunction "C_C") (pintype "passive"))
      (node (ref "LED151") (pin "C") (pinfunction "C_C") (pintype "passive"))
      (node (ref "LED152") (pin "C") (pinfunction "C_C") (pintype "passive"))
      (node (ref "LED153") (pin "C") (pinfunction "C_C") (pintype "passive"))
      (node (ref "LED154") (pin "C") (pinfunction "C_C") (pintype "passive"))
      (node (ref "LED155") (pin "C") (pinfunction "C_C") (pintype "passive"))
      (node (ref "LED156") (pin "C") (pinfunction "C_C") (pintype "passive"))
      (node (ref "LED157") (pin "C") (pinfunction "C_C") (pintype "passive"))
      (node (ref "LED158") (pin "C") (pinfunction "C_C") (pintype "passive"))
      (node (ref "LED159") (pin "C") (pinfunction "C_C") (pintype "passive"))
      (node (ref "LED160") (pin "C") (pinfunction "C_C") (pintype "passive"))
      (node (ref "Q14") (pin "3") (pinfunction "D_3") (pintype "passive"))
    )
    (net (code "78") (name "Net-(Q16-D)") (class "Default")
      (node (ref "LED161") (pin "C") (pinfunction "C_C") (pintype "passive"))
      (node (ref "LED162") (pin "C") (pinfunction "C_C") (pintype "passive"))
      (node (ref "LED163") (pin "C") (pinfunction "C_C") (pintype "passive"))
      (node (ref "LED164") (pin "C") (pinfunction "C_C") (pintype "passive"))
      (node (ref "LED165") (pin "C") (pinfunction "C_C") (pintype "passive"))
      (node (ref "LED166") (pin "C") (pinfunction "C_C") (pintype "passive"))
      (node (ref "LED167") (pin "C") (pinfunction "C_C") (pintype "passive"))
      (node (ref "LED168") (pin "C") (pinfunction "C_C") (pintype "passive"))
      (node (ref "LED169") (pin "C") (pinfunction "C_C") (pintype "passive"))
      (node (ref "LED170") (pin "C") (pinfunction "C_C") (pintype "passive"))
      (node (ref "LED171") (pin "C") (pinfunction "C_C") (pintype "passive"))
      (node (ref "LED172") (pin "C") (pinfunction "C_C") (pintype "passive"))
      (node (ref "LED173") (pin "C") (pinfunction "C_C") (pintype "passive"))
      (node (ref "LED174") (pin "C") (pinfunction "C_C") (pintype "passive"))
      (node (ref "LED175") (pin "C") (pinfunction "C_C") (pintype "passive"))
      (node (ref "LED176") (pin "C") (pinfunction "C_C") (pintype "passive"))
      (node (ref "LED177") (pin "C") (pinfunction "C_C") (pintype "passive"))
      (node (ref "LED178") (pin "C") (pinfunction "C_C") (pintype "passive"))
      (node (ref "LED179") (pin "C") (pinfunction "C_C") (pintype "passive"))
      (node (ref "LED180") (pin "C") (pinfunction "C_C") (pintype "passive"))
      (node (ref "Q16") (pin "3") (pinfunction "D_3") (pintype "passive"))
    )
    (net (code "79") (name "Net-(Q19-D)") (class "Default")
      (node (ref "LED181") (pin "C") (pinfunction "C_C") (pintype "passive"))
      (node (ref "LED182") (pin "C") (pinfunction "C_C") (pintype "passive"))
      (node (ref "LED183") (pin "C") (pinfunction "C_C") (pintype "passive"))
      (node (ref "LED184") (pin "C") (pinfunction "C_C") (pintype "passive"))
      (node (ref "LED185") (pin "C") (pinfunction "C_C") (pintype "passive"))
      (node (ref "LED186") (pin "C") (pinfunction "C_C") (pintype "passive"))
      (node (ref "LED187") (pin "C") (pinfunction "C_C") (pintype "passive"))
      (node (ref "LED188") (pin "C") (pinfunction "C_C") (pintype "passive"))
      (node (ref "LED189") (pin "C") (pinfunction "C_C") (pintype "passive"))
      (node (ref "LED190") (pin "C") (pinfunction "C_C") (pintype "passive"))
      (node (ref "LED191") (pin "C") (pinfunction "C_C") (pintype "passive"))
      (node (ref "LED192") (pin "C") (pinfunction "C_C") (pintype "passive"))
      (node (ref "LED193") (pin "C") (pinfunction "C_C") (pintype "passive"))
      (node (ref "LED194") (pin "C") (pinfunction "C_C") (pintype "passive"))
      (node (ref "LED195") (pin "C") (pinfunction "C_C") (pintype "passive"))
      (node (ref "LED196") (pin "C") (pinfunction "C_C") (pintype "passive"))
      (node (ref "LED197") (pin "C") (pinfunction "C_C") (pintype "passive"))
      (node (ref "LED198") (pin "C") (pinfunction "C_C") (pintype "passive"))
      (node (ref "LED199") (pin "C") (pinfunction "C_C") (pintype "passive"))
      (node (ref "LED200") (pin "C") (pinfunction "C_C") (pintype "passive"))
      (node (ref "Q19") (pin "3") (pinfunction "D_3") (pintype "passive"))
    )
    (net (code "80") (name "Net-(SV2-Pad3)") (class "Default")
      (node (ref "SV2") (pin "3") (pinfunction "3_3") (pintype "passive"))
      (node (ref "SV4") (pin "3") (pinfunction "3_3") (pintype "passive"))
    )
    (net (code "81") (name "Net-(U1-PB1(OC1A))") (class "Default")
      (node (ref "R24") (pin "2") (pinfunction "2_2") (pintype "passive"))
      (node (ref "U1") (pin "13") (pinfunction "PB1(OC1A)_13") (pintype "bidirectional"))
    )
    (net (code "82") (name "Net-(U1-PB4(MISO))") (class "Default")
      (node (ref "R26") (pin "2") (pinfunction "2_2") (pintype "passive"))
      (node (ref "U1") (pin "16") (pinfunction "PB4(MISO)_16") (pintype "bidirectional"))
    )
    (net (code "83") (name "Net-(U1-PB6(XTAL1{slash}TOSC1))") (class "Default")
      (node (ref "C2") (pin "2") (pinfunction "2_2") (pintype "passive"))
      (node (ref "U1") (pin "7") (pinfunction "PB6(XTAL1/TOSC1)_7") (pintype "bidirectional"))
      (node (ref "Y1") (pin "3") (pinfunction "2_3") (pintype "passive"))
    )
    (net (code "84") (name "Net-(U1-PB7(XTAL2{slash}TOSC2))") (class "Default")
      (node (ref "C3") (pin "2") (pinfunction "2_2") (pintype "passive"))
      (node (ref "U1") (pin "8") (pinfunction "PB7(XTAL2/TOSC2)_8") (pintype "bidirectional"))
      (node (ref "Y1") (pin "1") (pinfunction "1_1") (pintype "passive"))
    )
    (net (code "85") (name "Net-(U1-PC0(ADC0))") (class "Default")
      (node (ref "R30") (pin "2") (pinfunction "2_2") (pintype "passive"))
      (node (ref "U1") (pin "23") (pinfunction "PC0(ADC0)_23") (pintype "bidirectional"))
    )
    (net (code "86") (name "Net-(U1-PC1(ADC1))") (class "Default")
      (node (ref "R31") (pin "2") (pinfunction "2_2") (pintype "passive"))
      (node (ref "U1") (pin "24") (pinfunction "PC1(ADC1)_24") (pintype "bidirectional"))
    )
    (net (code "87") (name "Net-(U1-PC2(ADC2))") (class "Default")
      (node (ref "R32") (pin "2") (pinfunction "2_2") (pintype "passive"))
      (node (ref "U1") (pin "25") (pinfunction "PC2(ADC2)_25") (pintype "bidirectional"))
    )
    (net (code "88") (name "Net-(U1-PC3(ADC3))") (class "Default")
      (node (ref "R33") (pin "2") (pinfunction "2_2") (pintype "passive"))
      (node (ref "U1") (pin "26") (pinfunction "PC3(ADC3)_26") (pintype "bidirectional"))
    )
    (net (code "89") (name "Net-(U1-PC4(ADC4{slash}SDA))") (class "Default")
      (node (ref "R34") (pin "2") (pinfunction "2_2") (pintype "passive"))
      (node (ref "U1") (pin "27") (pinfunction "PC4(ADC4/SDA)_27") (pintype "bidirectional"))
    )
    (net (code "90") (name "Net-(U1-PC5(ADC5{slash}SCL))") (class "Default")
      (node (ref "R35") (pin "2") (pinfunction "2_2") (pintype "passive"))
      (node (ref "U1") (pin "28") (pinfunction "PC5(ADC5/SCL)_28") (pintype "bidirectional"))
    )
    (net (code "91") (name "Net-(U1-PC6({slash}RESET))") (class "Default")
      (node (ref "C1") (pin "2") (pinfunction "2_2") (pintype "passive"))
      (node (ref "R21") (pin "1") (pinfunction "1_1") (pintype "passive"))
      (node (ref "U1") (pin "29") (pinfunction "PC6(/RESET)_29") (pintype "bidirectional"))
    )
    (net (code "92") (name "Net-(U1-PD3(INT1))") (class "Default")
      (node (ref "R36") (pin "2") (pinfunction "2_2") (pintype "passive"))
      (node (ref "U1") (pin "1") (pinfunction "PD3(INT1)_1") (pintype "bidirectional"))
    )
    (net (code "93") (name "Net-(U1-PD4(XCK{slash}T0))") (class "Default")
      (node (ref "R37") (pin "2") (pinfunction "2_2") (pintype "passive"))
      (node (ref "U1") (pin "2") (pinfunction "PD4(XCK/T0)_2") (pintype "bidirectional"))
    )
    (net (code "94") (name "Net-(U1-PD5(T1))") (class "Default")
      (node (ref "R23") (pin "2") (pinfunction "2_2") (pintype "passive"))
      (node (ref "U1") (pin "9") (pinfunction "PD5(T1)_9") (pintype "bidirectional"))
    )
    (net (code "95") (name "Net-(U1-PD7(AIN1))") (class "Default")
      (node (ref "R40") (pin "2") (pinfunction "2_2") (pintype "passive"))
      (node (ref "U1") (pin "11") (pinfunction "PD7(AIN1)_11") (pintype "bidirectional"))
    )
    (net (code "96") (name "Net-(U3-PROG)") (class "Default")
      (node (ref "2K") (pin "1") (pinfunction "1_1") (pintype "passive"))
      (node (ref "U3") (pin "5") (pinfunction "PROG_5") (pintype "input"))
    )
    (net (code "97") (name "Net-(U3-STAT)") (class "Default")
      (node (ref "470R") (pin "2") (pinfunction "2_2") (pintype "passive"))
      (node (ref "U3") (pin "1") (pinfunction "STAT_1") (pintype "output"))
    )
    (net (code "98") (name "unconnected-(IC1-QA-Pad15)") (class "Default")
      (node (ref "IC1") (pin "15") (pinfunction "QA_15") (pintype "tri_state"))
    )
    (net (code "99") (name "unconnected-(IC3-QA-Pad15)") (class "Default")
      (node (ref "IC3") (pin "15") (pinfunction "QA_15") (pintype "tri_state"))
    )
    (net (code "100") (name "unconnected-(IC3-QG-Pad6)") (class "Default")
      (node (ref "IC3") (pin "6") (pinfunction "QG_6") (pintype "tri_state"))
    )
    (net (code "101") (name "unconnected-(IC3-QH*-Pad9)") (class "Default")
      (node (ref "IC3") (pin "9") (pinfunction "QH*_9") (pintype "tri_state"))
    )
    (net (code "102") (name "unconnected-(IC3-QH-Pad7)") (class "Default")
      (node (ref "IC3") (pin "7") (pinfunction "QH_7") (pintype "tri_state"))
    )
    (net (code "103") (name "unconnected-(SV4-Pad1)") (class "Default")
      (node (ref "SV4") (pin "1") (pinfunction "1_1") (pintype "passive"))
    )
    (net (code "104") (name "unconnected-(X2-Pad2)") (class "Default")
      (node (ref "X2") (pin "2") (pinfunction "2_2") (pintype "passive"))
    )
    (net (code "105") (name "unconnected-(X2-Pad3)") (class "Default")
      (node (ref "X2") (pin "3") (pinfunction "3_3") (pintype "passive"))
    )
    (net (code "106") (name "unconnected-(X2-Pad4)") (class "Default")
      (node (ref "X2") (pin "4") (pinfunction "4_4") (pintype "passive"))
    )
  )
)
